# DigitalStethoscope.net
KiCad netlist of a schematic drawn in EAGLE
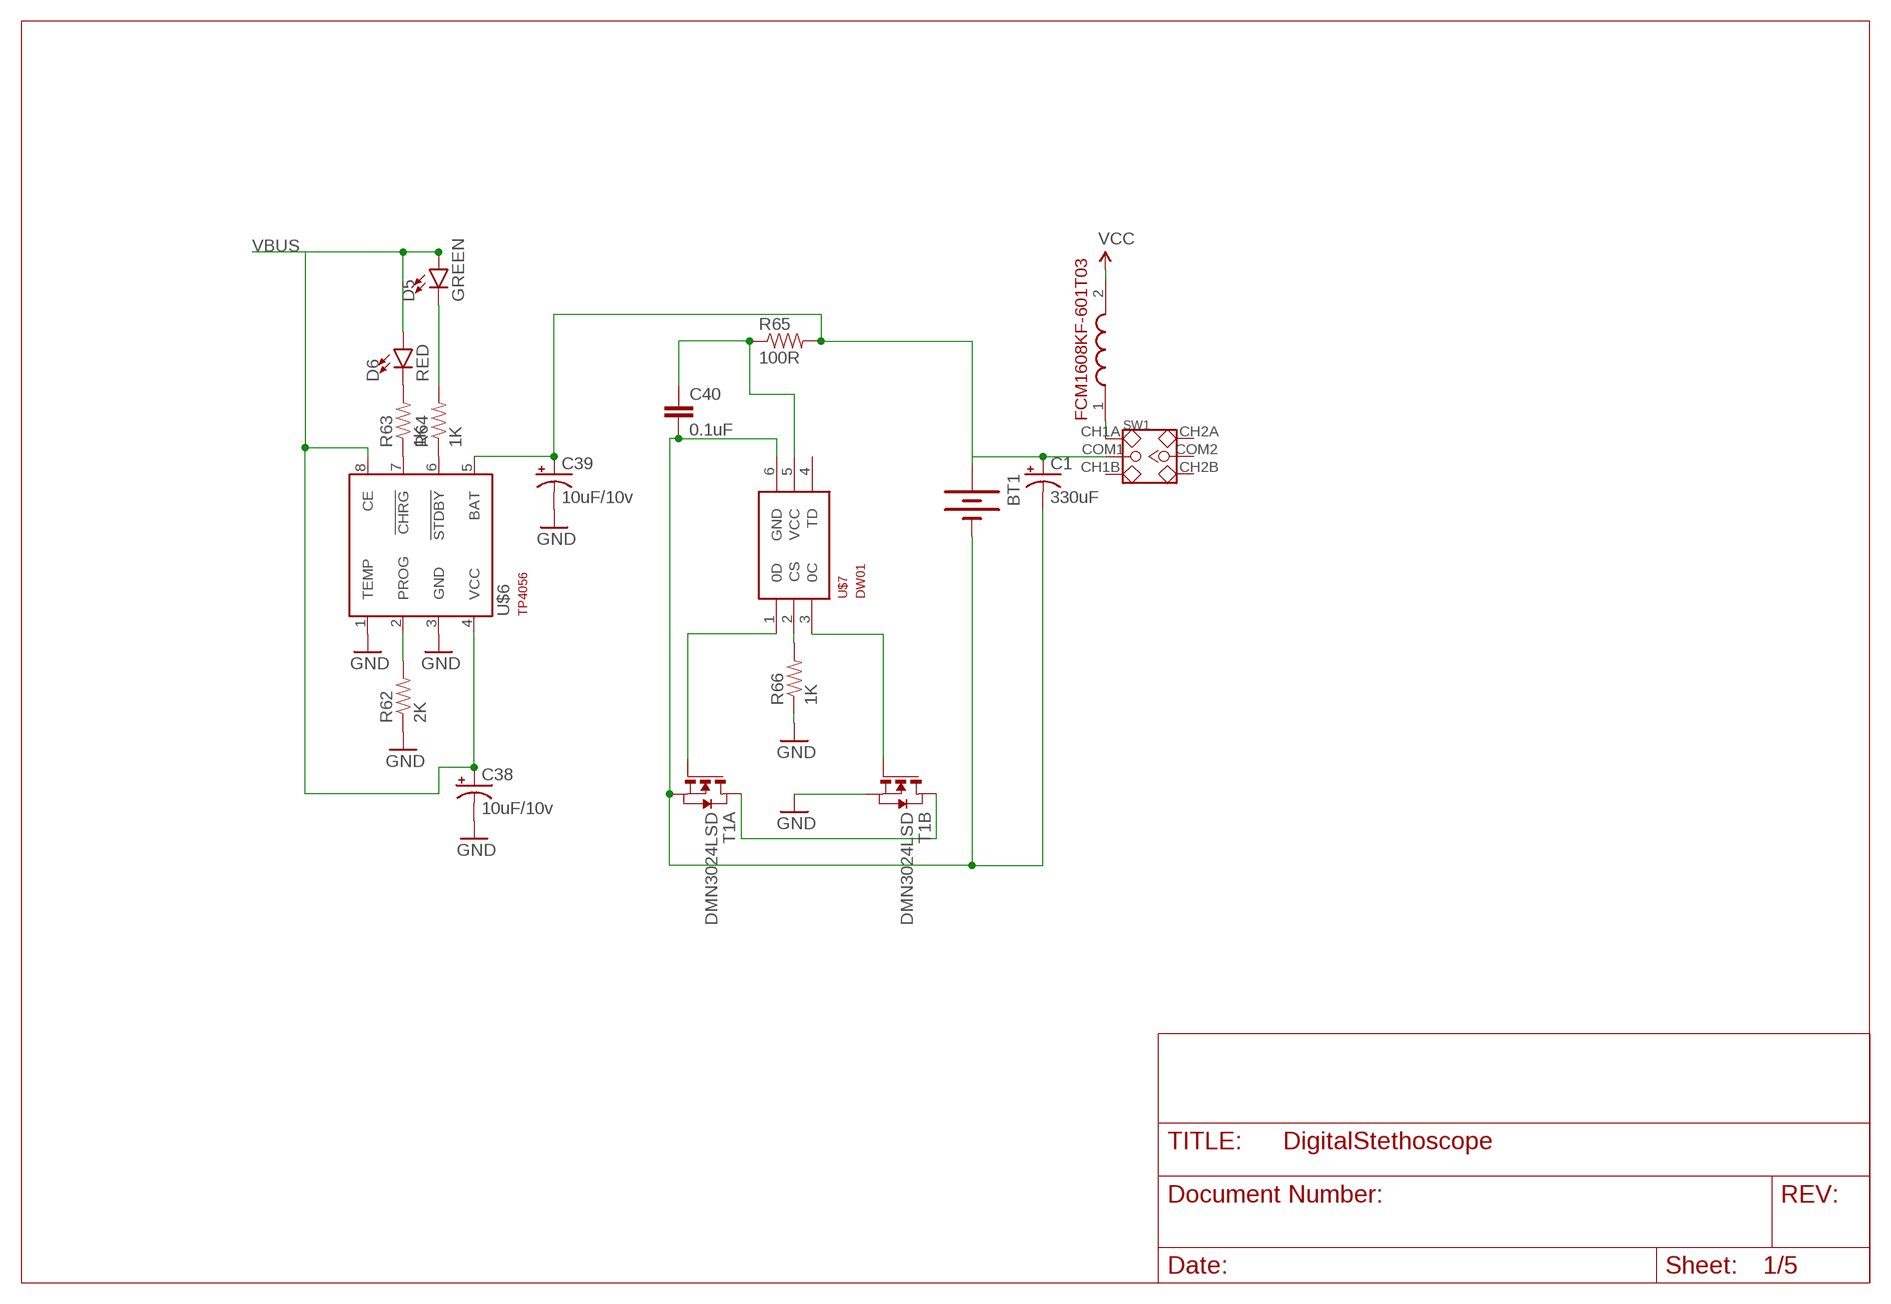
[diagram p0: schematic, sheet 1]
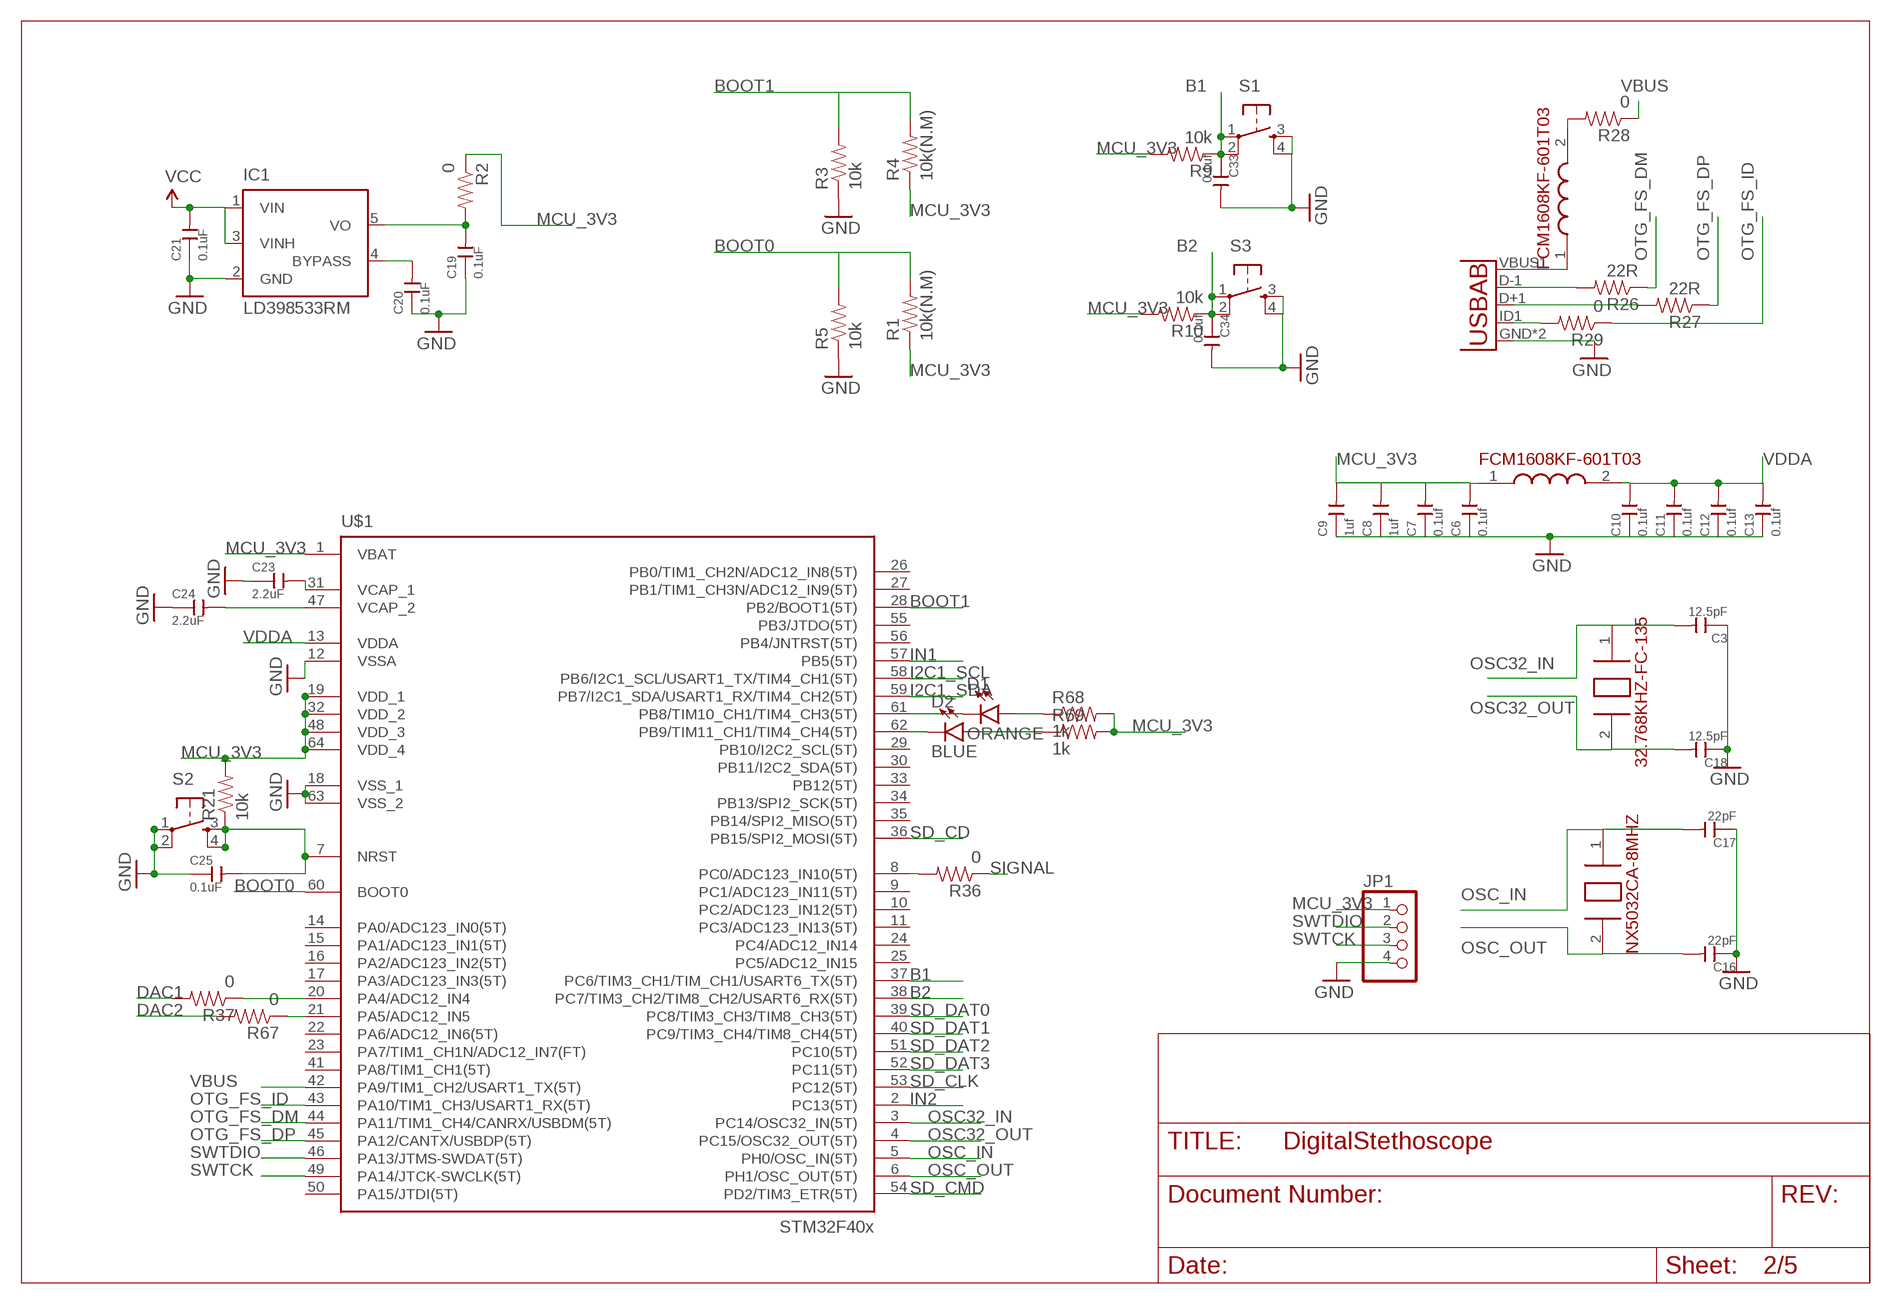
[diagram p1: schematic, sheet 2]
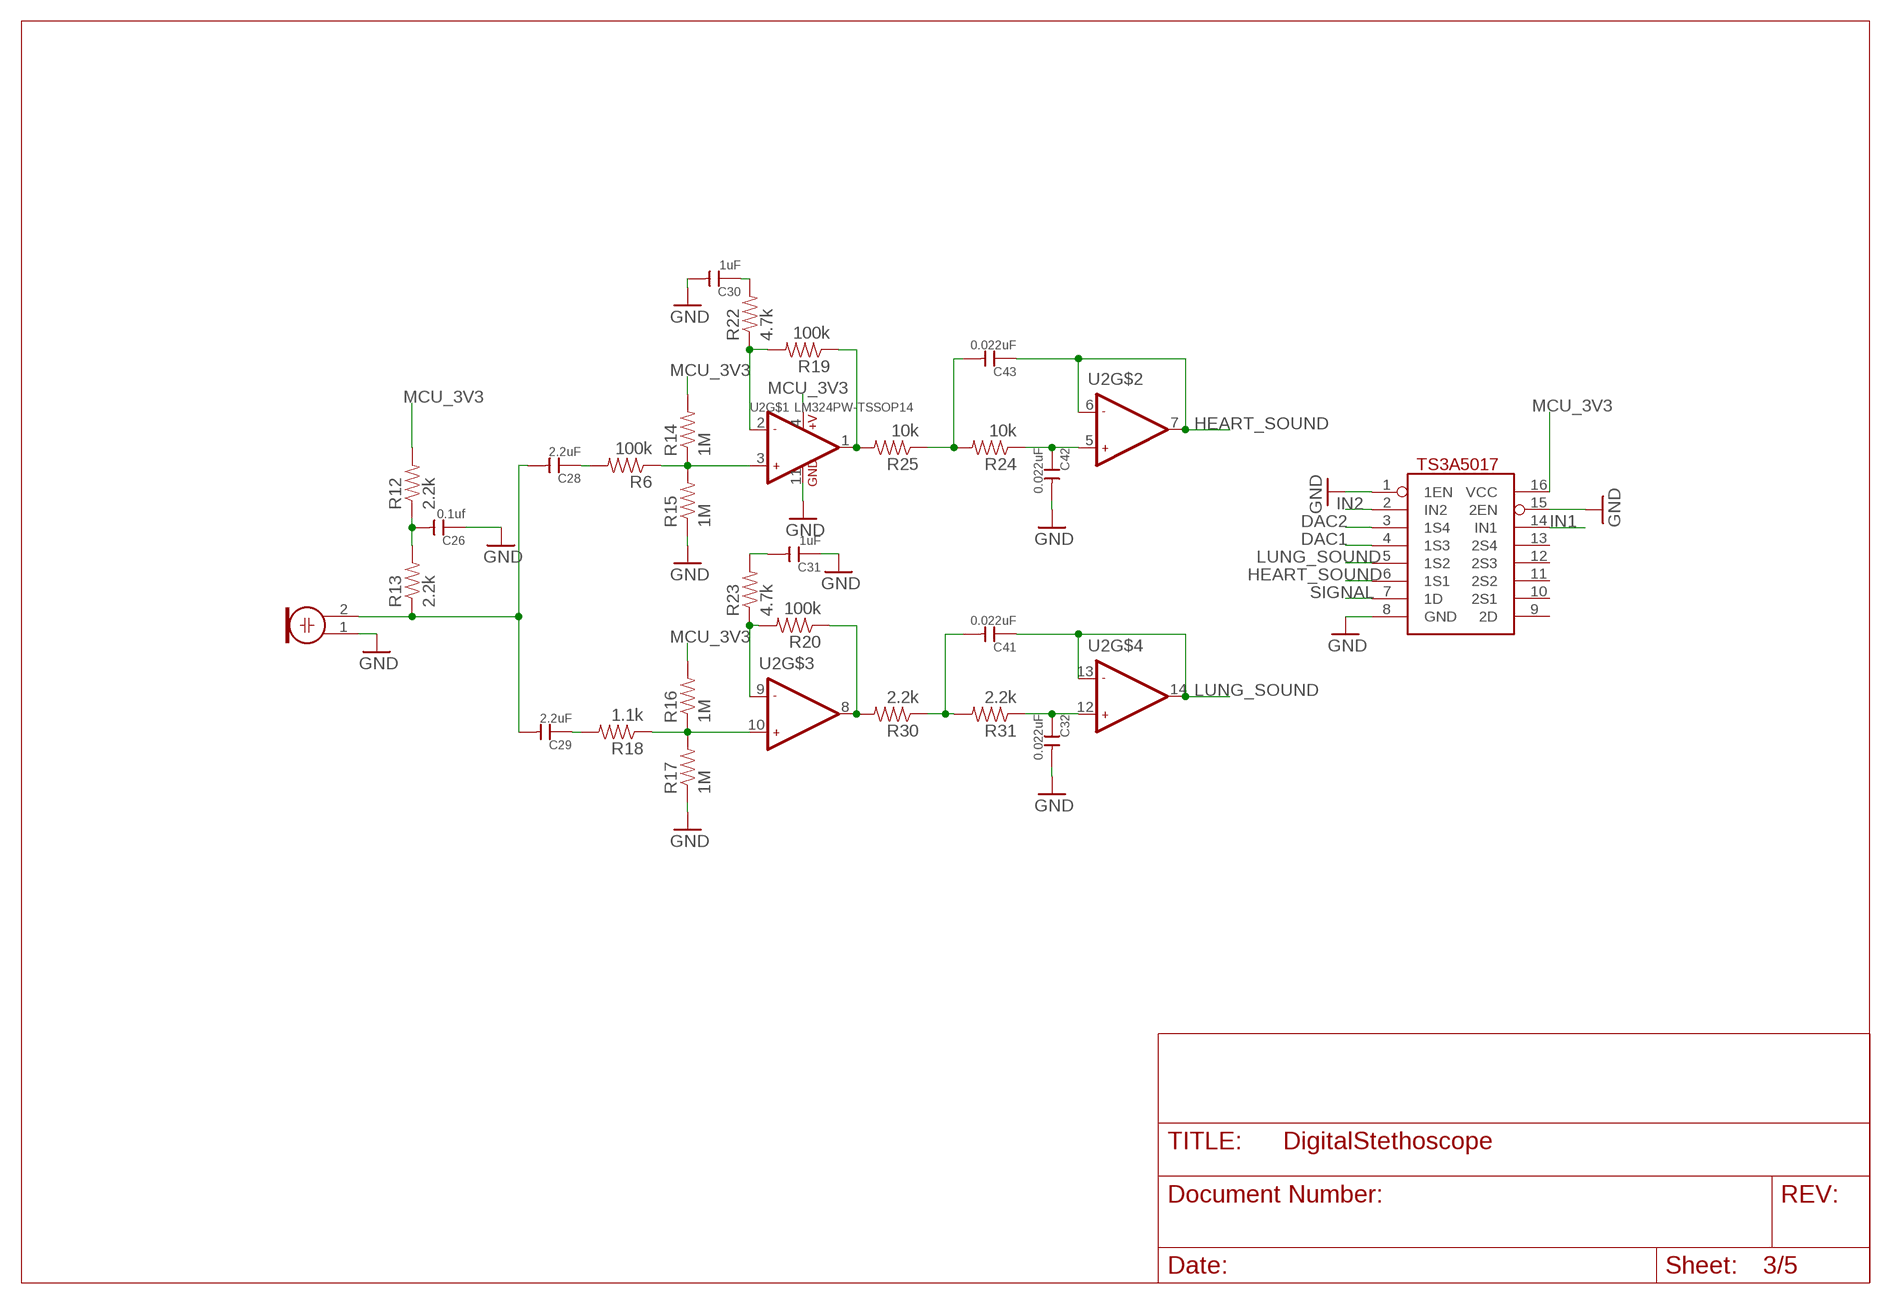
[diagram p2: schematic, sheet 3]
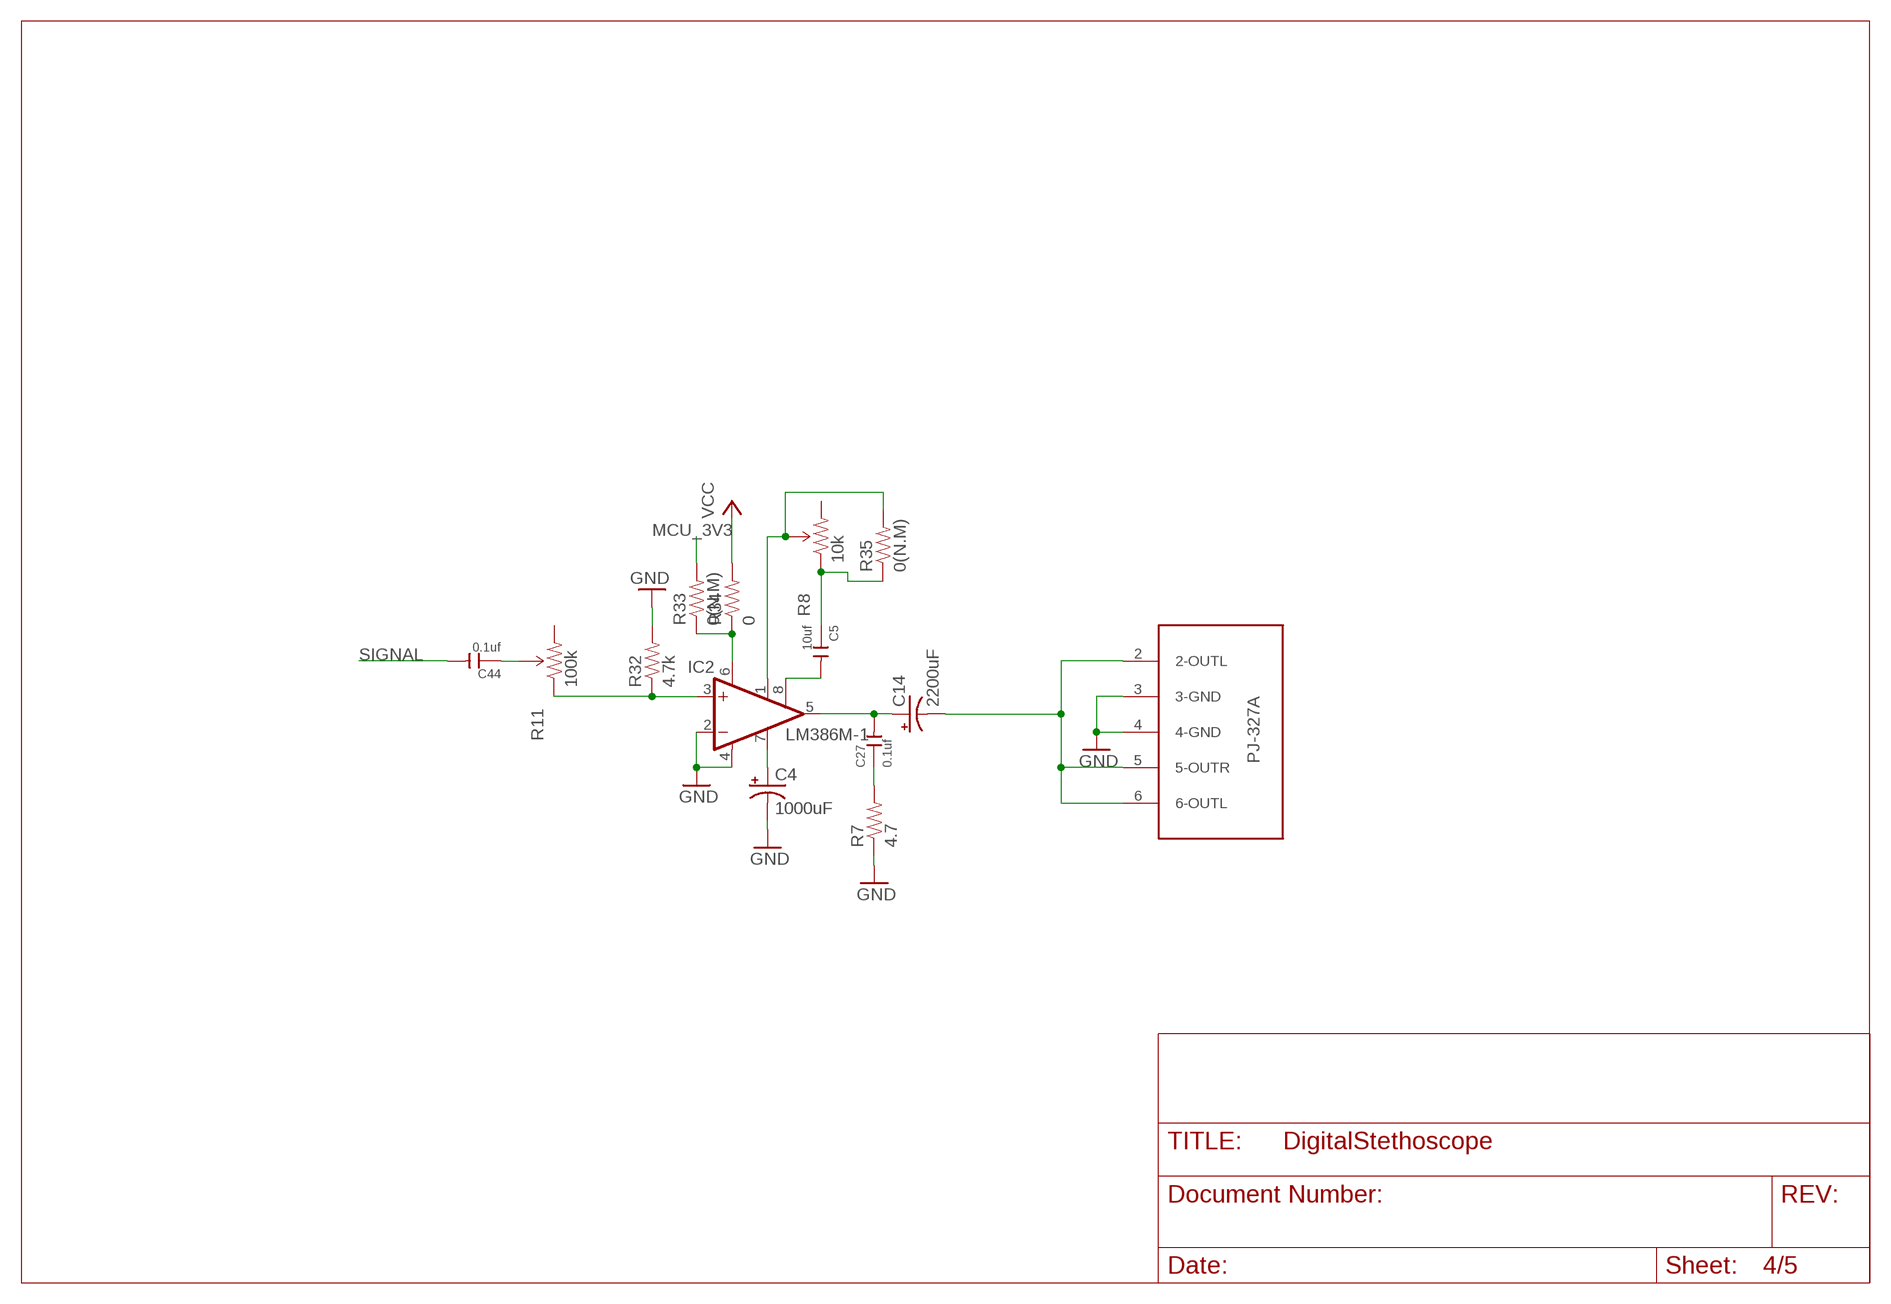
[diagram p3: schematic, sheet 4]
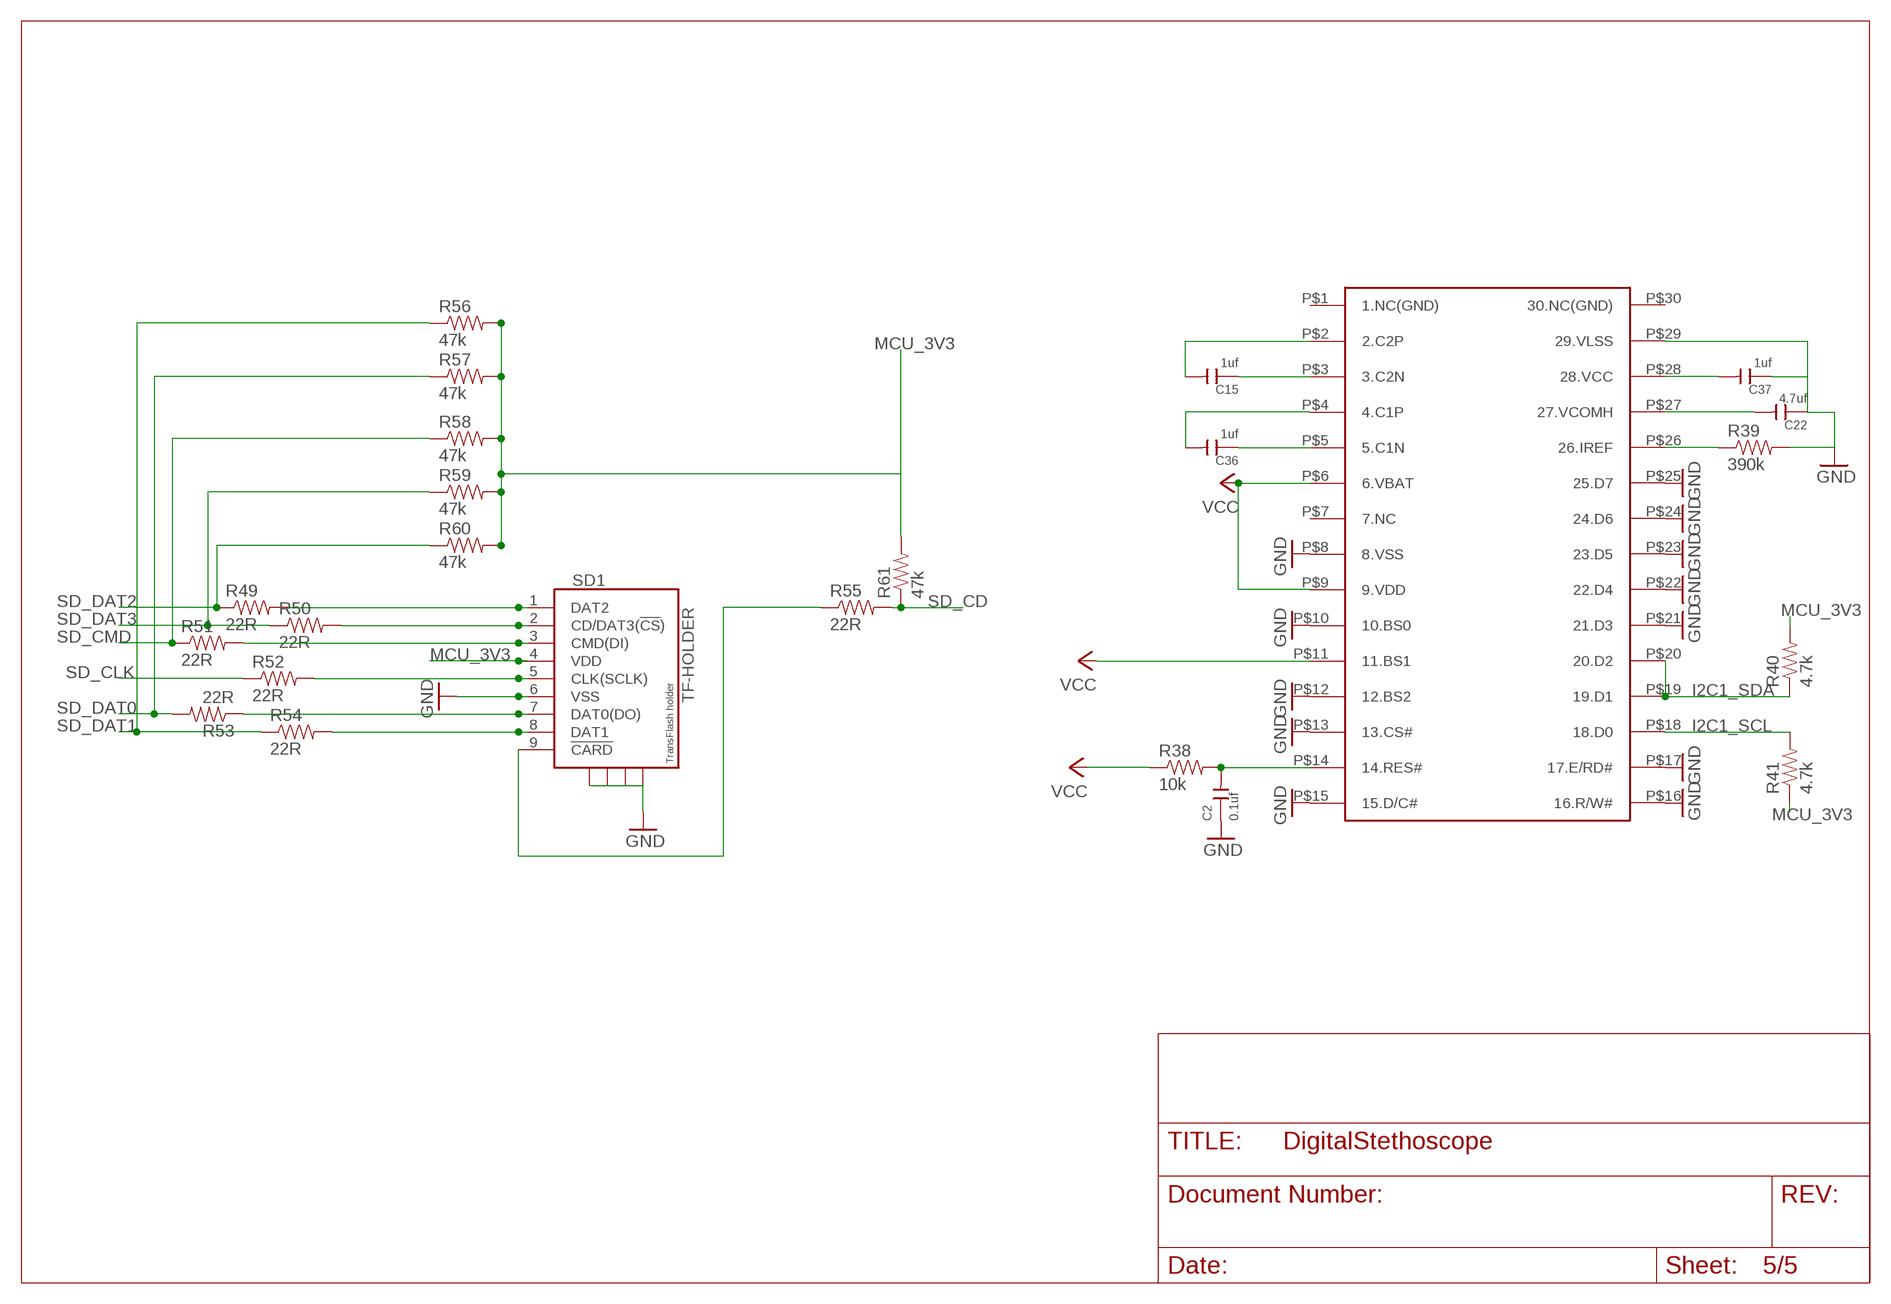
[diagram p4: schematic, sheet 5]

(export (version "E")
  (design (tool "Eeschema 10.0.6"))
  (components
    (comp (ref "C3")
      (value "12.5pF")
      (footprint "eagle-import:C0603")
      (fields (field (name "MPN") "CC0603KRX5R6BB475"))
      (libsource (lib "eagle-import") (part "CERAMIC-4.7UF-10V-10%-X5R(0603)"))
    )
    (comp (ref "C6")
      (value "0.1uf")
      (footprint "eagle-import:C0603")
      (fields (field (name "MPN") "CC0603KRX5R6BB475"))
      (libsource (lib "eagle-import") (part "CERAMIC-4.7UF-10V-10%-X5R(0603)"))
    )
    (comp (ref "C7")
      (value "0.1uf")
      (footprint "eagle-import:C0603")
      (fields (field (name "MPN") "CC0603KRX5R6BB475"))
      (libsource (lib "eagle-import") (part "CERAMIC-4.7UF-10V-10%-X5R(0603)"))
    )
    (comp (ref "C8")
      (value "1uf")
      (footprint "eagle-import:C0603")
      (fields (field (name "MPN") "CC0603KRX5R6BB475"))
      (libsource (lib "eagle-import") (part "CERAMIC-4.7UF-10V-10%-X5R(0603)"))
    )
    (comp (ref "C9")
      (value "1uf")
      (footprint "eagle-import:C0603")
      (fields (field (name "MPN") "CC0603KRX5R6BB475"))
      (libsource (lib "eagle-import") (part "CERAMIC-4.7UF-10V-10%-X5R(0603)"))
    )
    (comp (ref "C10")
      (value "0.1uf")
      (footprint "eagle-import:C0603")
      (fields (field (name "MPN") "CC0603KRX5R6BB475"))
      (libsource (lib "eagle-import") (part "CERAMIC-4.7UF-10V-10%-X5R(0603)"))
    )
    (comp (ref "C11")
      (value "0.1uf")
      (footprint "eagle-import:C0603")
      (fields (field (name "MPN") "CC0603KRX5R6BB475"))
      (libsource (lib "eagle-import") (part "CERAMIC-4.7UF-10V-10%-X5R(0603)"))
    )
    (comp (ref "C12")
      (value "0.1uf")
      (footprint "eagle-import:C0603")
      (fields (field (name "MPN") "CC0603KRX5R6BB475"))
      (libsource (lib "eagle-import") (part "CERAMIC-4.7UF-10V-10%-X5R(0603)"))
    )
    (comp (ref "C13")
      (value "0.1uf")
      (footprint "eagle-import:C0603")
      (fields (field (name "MPN") "CC0603KRX5R6BB475"))
      (libsource (lib "eagle-import") (part "CERAMIC-4.7UF-10V-10%-X5R(0603)"))
    )
    (comp (ref "C16")
      (value "22pF")
      (footprint "eagle-import:C0603")
      (fields (field (name "MPN") "CC0603KRX5R6BB475"))
      (libsource (lib "eagle-import") (part "CERAMIC-4.7UF-10V-10%-X5R(0603)"))
    )
    (comp (ref "C17")
      (value "22pF")
      (footprint "eagle-import:C0603")
      (fields (field (name "MPN") "CC0603KRX5R6BB475"))
      (libsource (lib "eagle-import") (part "CERAMIC-4.7UF-10V-10%-X5R(0603)"))
    )
    (comp (ref "C18")
      (value "12.5pF")
      (footprint "eagle-import:C0603")
      (fields (field (name "MPN") "CC0603KRX5R6BB475"))
      (libsource (lib "eagle-import") (part "CERAMIC-4.7UF-10V-10%-X5R(0603)"))
    )
    (comp (ref "C19")
      (value "0.1uF")
      (footprint "eagle-import:C0603")
      (libsource (lib "eagle-import") (part "CERAMIC-0.5PF-50V-0.1PF-NPO(0603)"))
    )
    (comp (ref "C20")
      (value "0.1uF")
      (footprint "eagle-import:C0603")
      (libsource (lib "eagle-import") (part "CERAMIC-0.5PF-50V-0.1PF-NPO(0603)"))
    )
    (comp (ref "C21")
      (value "0.1uF")
      (footprint "eagle-import:C0603")
      (libsource (lib "eagle-import") (part "CERAMIC-0.5PF-50V-0.1PF-NPO(0603)"))
    )
    (comp (ref "C23")
      (value "2.2uF")
      (footprint "eagle-import:C0603")
      (libsource (lib "eagle-import") (part "CERAMIC-0.5PF-50V-0.1PF-NPO(0603)"))
    )
    (comp (ref "C24")
      (value "2.2uF")
      (footprint "eagle-import:C0603")
      (libsource (lib "eagle-import") (part "CERAMIC-0.5PF-50V-0.1PF-NPO(0603)"))
    )
    (comp (ref "C25")
      (value "0.1uF")
      (footprint "eagle-import:C0603")
      (libsource (lib "eagle-import") (part "CERAMIC-0.5PF-50V-0.1PF-NPO(0603)"))
    )
    (comp (ref "C33")
      (value "0.1uf")
      (footprint "eagle-import:C0603")
      (fields (field (name "MPN") "CC0603KRX5R6BB475"))
      (libsource (lib "eagle-import") (part "CERAMIC-4.7UF-10V-10%-X5R(0603)"))
    )
    (comp (ref "C34")
      (value "0.1uf")
      (footprint "eagle-import:C0603")
      (fields (field (name "MPN") "CC0603KRX5R6BB475"))
      (libsource (lib "eagle-import") (part "CERAMIC-4.7UF-10V-10%-X5R(0603)"))
    )
    (comp (ref "D1")
      (value "ORANGE")
      (footprint "eagle-import:LED-0603")
      (libsource (lib "eagle-import") (part "LED-BLUE0603"))
    )
    (comp (ref "D2")
      (value "BLUE")
      (footprint "eagle-import:LED-0603")
      (libsource (lib "eagle-import") (part "LED-BLUE0603"))
    )
    (comp (ref "IC1")
      (value "LD398533RM")
      (footprint "eagle-import:SOT23-5L")
      (libsource (lib "eagle-import") (part "LD3985M33R"))
    )
    (comp (ref "JP1")
      (value "PINHD-1X4")
      (footprint "eagle-import:1X04")
      (libsource (lib "eagle-import") (part "PINHD-1X4"))
    )
    (comp (ref "R1")
      (value "10k(N.M)")
      (footprint "eagle-import:0603")
      (libsource (lib "eagle-import") (part "0OHM1/10W5%(0603)"))
    )
    (comp (ref "R2")
      (value "0")
      (footprint "eagle-import:0603-RES")
      (libsource (lib "eagle-import") (part "390OHM1/10W1%(0603)"))
    )
    (comp (ref "R3")
      (value "10k")
      (footprint "eagle-import:0603")
      (libsource (lib "eagle-import") (part "0OHM1/10W5%(0603)"))
    )
    (comp (ref "R4")
      (value "10k(N.M)")
      (footprint "eagle-import:0603")
      (libsource (lib "eagle-import") (part "0OHM1/10W5%(0603)"))
    )
    (comp (ref "R5")
      (value "10k")
      (footprint "eagle-import:0603")
      (libsource (lib "eagle-import") (part "0OHM1/10W5%(0603)"))
    )
    (comp (ref "R9")
      (value "10k")
      (footprint "eagle-import:0603")
      (libsource (lib "eagle-import") (part "0OHM1/10W5%(0603)"))
    )
    (comp (ref "R10")
      (value "10k")
      (footprint "eagle-import:0603")
      (libsource (lib "eagle-import") (part "0OHM1/10W5%(0603)"))
    )
    (comp (ref "R21")
      (value "10k")
      (footprint "eagle-import:0603-RES")
      (libsource (lib "eagle-import") (part "390OHM1/10W1%(0603)"))
    )
    (comp (ref "R26")
      (value "22R")
      (footprint "eagle-import:0603-RES")
      (libsource (lib "eagle-import") (part "390OHM1/10W1%(0603)"))
    )
    (comp (ref "R27")
      (value "22R")
      (footprint "eagle-import:0603-RES")
      (libsource (lib "eagle-import") (part "390OHM1/10W1%(0603)"))
    )
    (comp (ref "R28")
      (value "0")
      (footprint "eagle-import:0603-RES")
      (libsource (lib "eagle-import") (part "390OHM1/10W1%(0603)"))
    )
    (comp (ref "R29")
      (value "0")
      (footprint "eagle-import:0603-RES")
      (libsource (lib "eagle-import") (part "390OHM1/10W1%(0603)"))
    )
    (comp (ref "R36")
      (value "0")
      (footprint "eagle-import:0603-RES")
      (libsource (lib "eagle-import") (part "390OHM1/10W1%(0603)"))
    )
    (comp (ref "R37")
      (value "0")
      (footprint "eagle-import:0603-RES")
      (libsource (lib "eagle-import") (part "390OHM1/10W1%(0603)"))
    )
    (comp (ref "R67")
      (value "0")
      (footprint "eagle-import:0603-RES")
      (libsource (lib "eagle-import") (part "390OHM1/10W1%(0603)"))
    )
    (comp (ref "R68")
      (value "1k")
      (footprint "eagle-import:0603-RES")
      (libsource (lib "eagle-import") (part "390OHM1/10W1%(0603)"))
    )
    (comp (ref "R69")
      (value "1k")
      (footprint "eagle-import:0603-RES")
      (libsource (lib "eagle-import") (part "390OHM1/10W1%(0603)"))
    )
    (comp (ref "S1")
      (value "TAC_SWITCHSMD")
      (footprint "eagle-import:TACTILE_SWITCH_SMD")
      (libsource (lib "eagle-import") (part "TAC_SWITCHSMD"))
    )
    (comp (ref "S2")
      (value "TAC_SWITCHSMD")
      (footprint "eagle-import:TACTILE_SWITCH_SMD")
      (libsource (lib "eagle-import") (part "TAC_SWITCHSMD"))
    )
    (comp (ref "S3")
      (value "TAC_SWITCHSMD")
      (footprint "eagle-import:TACTILE_SWITCH_SMD")
      (libsource (lib "eagle-import") (part "TAC_SWITCHSMD"))
    )
    (comp (ref "U$1")
      (value "STM32F405R")
      (footprint "eagle-import:TQFP64")
      (libsource (lib "eagle-import") (part "STM32F405R"))
    )
    (comp (ref "U$2")
      (value "32.768KHZ-FC-135")
      (footprint "eagle-import:32.768KHZ-FC-135")
      (libsource (lib "eagle-import") (part "32.768KHZ-FC-135"))
    )
    (comp (ref "U$3")
      (value "FCM1608KF-601T03")
      (footprint "eagle-import:FCM1608KF-601T03")
      (libsource (lib "eagle-import") (part "FCM1608KF-601T03"))
    )
    (comp (ref "U$5")
      (value "FCM1608KF-601T03")
      (footprint "eagle-import:FCM1608KF-601T03")
      (libsource (lib "eagle-import") (part "FCM1608KF-601T03"))
    )
    (comp (ref "U$8")
      (value "NX5032CA-8MHZ")
      (footprint "eagle-import:NX5032CA-8MHZ")
      (libsource (lib "eagle-import") (part "NX5032CA-8MHZ"))
    )
    (comp (ref "U4")
      (value "USB\"\"")
      (footprint "eagle-import:USB-MICRO-SMD")
      (libsource (lib "eagle-import") (part "USB{dblquote}{dblquote}"))
    )
    (comp (ref "C2")
      (value "0.1uf")
      (footprint "eagle-import:C0603")
      (fields (field (name "MPN") "CC0603KRX5R6BB475"))
      (libsource (lib "eagle-import") (part "CERAMIC-4.7UF-10V-10%-X5R(0603)"))
    )
    (comp (ref "C15")
      (value "1uf")
      (footprint "eagle-import:C0603")
      (fields (field (name "MPN") "CC0603KRX5R6BB475"))
      (libsource (lib "eagle-import") (part "CERAMIC-4.7UF-10V-10%-X5R(0603)"))
    )
    (comp (ref "C22")
      (value "4.7uf")
      (footprint "eagle-import:C0603")
      (fields (field (name "MPN") "CC0603KRX5R6BB475"))
      (libsource (lib "eagle-import") (part "CERAMIC-4.7UF-10V-10%-X5R(0603)"))
    )
    (comp (ref "C36")
      (value "1uf")
      (footprint "eagle-import:C0603")
      (fields (field (name "MPN") "CC0603KRX5R6BB475"))
      (libsource (lib "eagle-import") (part "CERAMIC-4.7UF-10V-10%-X5R(0603)"))
    )
    (comp (ref "C37")
      (value "1uf")
      (footprint "eagle-import:C0603")
      (fields (field (name "MPN") "CC0603KRX5R6BB475"))
      (libsource (lib "eagle-import") (part "CERAMIC-4.7UF-10V-10%-X5R(0603)"))
    )
    (comp (ref "R38")
      (value "10k")
      (footprint "eagle-import:0603")
      (libsource (lib "eagle-import") (part "0OHM1/10W5%(0603)"))
    )
    (comp (ref "R39")
      (value "390k")
      (footprint "eagle-import:0603")
      (libsource (lib "eagle-import") (part "0OHM1/10W5%(0603)"))
    )
    (comp (ref "R40")
      (value "4.7k")
      (footprint "eagle-import:0603")
      (libsource (lib "eagle-import") (part "0OHM1/10W5%(0603)"))
    )
    (comp (ref "R41")
      (value "4.7k")
      (footprint "eagle-import:0603")
      (libsource (lib "eagle-import") (part "0OHM1/10W5%(0603)"))
    )
    (comp (ref "R49")
      (value "22R")
      (footprint "eagle-import:0603-RES")
      (libsource (lib "eagle-import") (part "100OHM1/10W1%(0603)"))
    )
    (comp (ref "R50")
      (value "22R")
      (footprint "eagle-import:0603-RES")
      (libsource (lib "eagle-import") (part "100OHM1/10W1%(0603)"))
    )
    (comp (ref "R51")
      (value "22R")
      (footprint "eagle-import:0603-RES")
      (libsource (lib "eagle-import") (part "100OHM1/10W1%(0603)"))
    )
    (comp (ref "R52")
      (value "22R")
      (footprint "eagle-import:0603-RES")
      (libsource (lib "eagle-import") (part "100OHM1/10W1%(0603)"))
    )
    (comp (ref "R53")
      (value "22R")
      (footprint "eagle-import:0603-RES")
      (libsource (lib "eagle-import") (part "100OHM1/10W1%(0603)"))
    )
    (comp (ref "R54")
      (value "22R")
      (footprint "eagle-import:0603-RES")
      (libsource (lib "eagle-import") (part "100OHM1/10W1%(0603)"))
    )
    (comp (ref "R55")
      (value "22R")
      (footprint "eagle-import:0603-RES")
      (libsource (lib "eagle-import") (part "100OHM1/10W1%(0603)"))
    )
    (comp (ref "R56")
      (value "47k")
      (footprint "eagle-import:0603-RES")
      (libsource (lib "eagle-import") (part "100OHM1/10W1%(0603)"))
    )
    (comp (ref "R57")
      (value "47k")
      (footprint "eagle-import:0603-RES")
      (libsource (lib "eagle-import") (part "100OHM1/10W1%(0603)"))
    )
    (comp (ref "R58")
      (value "47k")
      (footprint "eagle-import:0603-RES")
      (libsource (lib "eagle-import") (part "100OHM1/10W1%(0603)"))
    )
    (comp (ref "R59")
      (value "47k")
      (footprint "eagle-import:0603-RES")
      (libsource (lib "eagle-import") (part "100OHM1/10W1%(0603)"))
    )
    (comp (ref "R60")
      (value "47k")
      (footprint "eagle-import:0603-RES")
      (libsource (lib "eagle-import") (part "100OHM1/10W1%(0603)"))
    )
    (comp (ref "R61")
      (value "47k")
      (footprint "eagle-import:0603-RES")
      (libsource (lib "eagle-import") (part "100OHM1/10W1%(0603)"))
    )
    (comp (ref "SD1")
      (value "TF-HOLDER")
      (footprint "eagle-import:TF-PULL")
      (libsource (lib "eagle-import") (part "TF-HOLDER"))
    )
    (comp (ref "U$18")
      (value "ER-OLED0.96")
      (footprint "eagle-import:ER-OLED0.96")
      (libsource (lib "eagle-import") (part "ER-OLED0.96"))
    )
    (comp (ref "C4")
      (value "1000uF")
      (footprint "eagle-import:E3,5-8")
      (libsource (lib "eagle-import") (part "CPOL-USE3.5-8"))
    )
    (comp (ref "C5")
      (value "10uf")
      (footprint "eagle-import:C0603")
      (fields (field (name "MPN") "CC0603KRX5R6BB475"))
      (libsource (lib "eagle-import") (part "CERAMIC-4.7UF-10V-10%-X5R(0603)"))
    )
    (comp (ref "C14")
      (value "2200uF")
      (footprint "eagle-import:E3,5-8")
      (libsource (lib "eagle-import") (part "CPOL-USE3.5-8"))
    )
    (comp (ref "C27")
      (value "0.1uf")
      (footprint "eagle-import:C0603")
      (fields (field (name "MPN") "CC0603KRX5R6BB475"))
      (libsource (lib "eagle-import") (part "CERAMIC-4.7UF-10V-10%-X5R(0603)"))
    )
    (comp (ref "C44")
      (value "0.1uf")
      (footprint "eagle-import:C0603")
      (fields (field (name "MPN") "CC0603KRX5R6BB475"))
      (libsource (lib "eagle-import") (part "CERAMIC-4.7UF-10V-10%-X5R(0603)"))
    )
    (comp (ref "IC2")
      (value "LM386M-1")
      (footprint "eagle-import:SO08")
      (libsource (lib "eagle-import") (part "LM386?-M1"))
    )
    (comp (ref "R7")
      (value "4.7")
      (footprint "eagle-import:0603-RES")
      (libsource (lib "eagle-import") (part "390OHM1/10W1%(0603)"))
    )
    (comp (ref "R8")
      (value "10k")
      (footprint "eagle-import:TRIMPOT_TC33")
      (libsource (lib "eagle-import") (part "TRIMPOT-2"))
    )
    (comp (ref "R11")
      (value "100k")
      (footprint "eagle-import:TRIMPOT_TC33")
      (libsource (lib "eagle-import") (part "TRIMPOT-2"))
    )
    (comp (ref "R32")
      (value "4.7k")
      (footprint "eagle-import:0603-RES")
      (libsource (lib "eagle-import") (part "390OHM1/10W1%(0603)"))
    )
    (comp (ref "R33")
      (value "0(N.M)")
      (footprint "eagle-import:0603-RES")
      (libsource (lib "eagle-import") (part "390OHM1/10W1%(0603)"))
    )
    (comp (ref "R34")
      (value "0")
      (footprint "eagle-import:0603-RES")
      (libsource (lib "eagle-import") (part "390OHM1/10W1%(0603)"))
    )
    (comp (ref "R35")
      (value "0(N.M)")
      (footprint "eagle-import:0603-RES")
      (libsource (lib "eagle-import") (part "390OHM1/10W1%(0603)"))
    )
    (comp (ref "U$9")
      (value "PJ-327A")
      (footprint "eagle-import:PJ-327A")
      (libsource (lib "eagle-import") (part "PJ-327A"))
    )
    (comp (ref "ASW")
      (value "MUX-TS3A5017")
      (footprint "eagle-import:SO16")
      (libsource (lib "eagle-import") (part "MUX-TS3A5017"))
    )
    (comp (ref "C26")
      (value "0.1uf")
      (footprint "eagle-import:C0603")
      (fields (field (name "MPN") "CC0603KRX5R6BB475"))
      (libsource (lib "eagle-import") (part "CERAMIC-4.7UF-10V-10%-X5R(0603)"))
    )
    (comp (ref "C28")
      (value "2.2uF")
      (footprint "eagle-import:C0603")
      (fields (field (name "MPN") "CC0603KRX5R6BB475"))
      (libsource (lib "eagle-import") (part "CERAMIC-4.7UF-10V-10%-X5R(0603)"))
    )
    (comp (ref "C29")
      (value "2.2uF")
      (footprint "eagle-import:C0603")
      (fields (field (name "MPN") "CC0603KRX5R6BB475"))
      (libsource (lib "eagle-import") (part "CERAMIC-4.7UF-10V-10%-X5R(0603)"))
    )
    (comp (ref "C30")
      (value "1uF")
      (footprint "eagle-import:C0603")
      (fields (field (name "MPN") "CC0603KRX5R6BB475"))
      (libsource (lib "eagle-import") (part "CERAMIC-4.7UF-10V-10%-X5R(0603)"))
    )
    (comp (ref "C31")
      (value "1uF")
      (footprint "eagle-import:C0603")
      (fields (field (name "MPN") "CC0603KRX5R6BB475"))
      (libsource (lib "eagle-import") (part "CERAMIC-4.7UF-10V-10%-X5R(0603)"))
    )
    (comp (ref "C32")
      (value "0.022uF")
      (footprint "eagle-import:C0603")
      (fields (field (name "MPN") "CC0603KRX5R6BB475"))
      (libsource (lib "eagle-import") (part "CERAMIC-4.7UF-10V-10%-X5R(0603)"))
    )
    (comp (ref "C41")
      (value "0.022uF")
      (footprint "eagle-import:C0603")
      (fields (field (name "MPN") "CC0603KRX5R6BB475"))
      (libsource (lib "eagle-import") (part "CERAMIC-4.7UF-10V-10%-X5R(0603)"))
    )
    (comp (ref "C42")
      (value "0.022uF")
      (footprint "eagle-import:C0603")
      (fields (field (name "MPN") "CC0603KRX5R6BB475"))
      (libsource (lib "eagle-import") (part "CERAMIC-4.7UF-10V-10%-X5R(0603)"))
    )
    (comp (ref "C43")
      (value "0.022uF")
      (footprint "eagle-import:C0603")
      (fields (field (name "MPN") "CC0603KRX5R6BB475"))
      (libsource (lib "eagle-import") (part "CERAMIC-4.7UF-10V-10%-X5R(0603)"))
    )
    (comp (ref "M1")
      (value "ELECTRET_MICROPHON-F6035AP")
      (footprint "eagle-import:F6035AP")
      (libsource (lib "eagle-import") (part "ELECTRET_MICROPHON-F6035AP"))
    )
    (comp (ref "R6")
      (value "100k")
      (footprint "eagle-import:0603-RES")
      (libsource (lib "eagle-import") (part "390OHM1/10W1%(0603)"))
    )
    (comp (ref "R12")
      (value "2.2k")
      (footprint "eagle-import:0603-RES")
      (libsource (lib "eagle-import") (part "390OHM1/10W1%(0603)"))
    )
    (comp (ref "R13")
      (value "2.2k")
      (footprint "eagle-import:0603-RES")
      (libsource (lib "eagle-import") (part "390OHM1/10W1%(0603)"))
    )
    (comp (ref "R14")
      (value "1M")
      (footprint "eagle-import:0603-RES")
      (libsource (lib "eagle-import") (part "390OHM1/10W1%(0603)"))
    )
    (comp (ref "R15")
      (value "1M")
      (footprint "eagle-import:0603-RES")
      (libsource (lib "eagle-import") (part "390OHM1/10W1%(0603)"))
    )
    (comp (ref "R16")
      (value "1M")
      (footprint "eagle-import:0603-RES")
      (libsource (lib "eagle-import") (part "390OHM1/10W1%(0603)"))
    )
    (comp (ref "R17")
      (value "1M")
      (footprint "eagle-import:0603-RES")
      (libsource (lib "eagle-import") (part "390OHM1/10W1%(0603)"))
    )
    (comp (ref "R18")
      (value "1.1k")
      (footprint "eagle-import:0603-RES")
      (libsource (lib "eagle-import") (part "390OHM1/10W1%(0603)"))
    )
    (comp (ref "R19")
      (value "100k")
      (footprint "eagle-import:0603-RES")
      (libsource (lib "eagle-import") (part "390OHM1/10W1%(0603)"))
    )
    (comp (ref "R20")
      (value "100k")
      (footprint "eagle-import:0603-RES")
      (libsource (lib "eagle-import") (part "390OHM1/10W1%(0603)"))
    )
    (comp (ref "R22")
      (value "4.7k")
      (footprint "eagle-import:0603-RES")
      (libsource (lib "eagle-import") (part "390OHM1/10W1%(0603)"))
    )
    (comp (ref "R23")
      (value "4.7k")
      (footprint "eagle-import:0603-RES")
      (libsource (lib "eagle-import") (part "390OHM1/10W1%(0603)"))
    )
    (comp (ref "R24")
      (value "10k")
      (footprint "eagle-import:0603-RES")
      (libsource (lib "eagle-import") (part "390OHM1/10W1%(0603)"))
    )
    (comp (ref "R25")
      (value "10k")
      (footprint "eagle-import:0603-RES")
      (libsource (lib "eagle-import") (part "390OHM1/10W1%(0603)"))
    )
    (comp (ref "R30")
      (value "2.2k")
      (footprint "eagle-import:0603-RES")
      (libsource (lib "eagle-import") (part "390OHM1/10W1%(0603)"))
    )
    (comp (ref "R31")
      (value "2.2k")
      (footprint "eagle-import:0603-RES")
      (libsource (lib "eagle-import") (part "390OHM1/10W1%(0603)"))
    )
    (comp (ref "U2")
      (value "LM324PW-TSSOP14")
      (footprint "eagle-import:TSSOP14-0.65-5X4.4MM")
      (fields (field (name "MPN") "LM324PW"))
      (libsource (lib "eagle-import") (part "AMPLIFIER-LM324PW(TSSOP14)"))
    )
    (comp (ref "BT1")
      (value "BATTERYLIPO-TABS")
      (footprint "eagle-import:LIPO-110-TABS")
      (libsource (lib "eagle-import") (part "BATTERYLIPO-TABS"))
    )
    (comp (ref "C1")
      (value "330uF")
      (footprint "eagle-import:E3,5-8")
      (libsource (lib "eagle-import") (part "CPOL-USE3.5-8"))
    )
    (comp (ref "C38")
      (value "10uF/10v")
      (footprint "eagle-import:EIA3216-KIT")
      (libsource (lib "eagle-import") (part "CAP_POL1206-KIT"))
    )
    (comp (ref "C39")
      (value "10uF/10v")
      (footprint "eagle-import:EIA3216-KIT")
      (libsource (lib "eagle-import") (part "CAP_POL1206-KIT"))
    )
    (comp (ref "C40")
      (value "0.1uF")
      (footprint "eagle-import:0603-CAP")
      (libsource (lib "eagle-import") (part "0.1UF-100V-10%(0603)"))
    )
    (comp (ref "D5")
      (value "GREEN")
      (footprint "eagle-import:LED-0603")
      (libsource (lib "eagle-import") (part "LED-BLUE0603"))
    )
    (comp (ref "D6")
      (value "RED")
      (footprint "eagle-import:LED-0603")
      (libsource (lib "eagle-import") (part "LED-BLUE0603"))
    )
    (comp (ref "R62")
      (value "2K")
      (footprint "eagle-import:0603-RES")
      (libsource (lib "eagle-import") (part "1KOHM1/10W1%(0603)"))
    )
    (comp (ref "R63")
      (value "1K")
      (footprint "eagle-import:0603-RES")
      (libsource (lib "eagle-import") (part "1KOHM1/10W1%(0603)"))
    )
    (comp (ref "R64")
      (value "1K")
      (footprint "eagle-import:0603-RES")
      (libsource (lib "eagle-import") (part "1KOHM1/10W1%(0603)"))
    )
    (comp (ref "R65")
      (value "100R")
      (footprint "eagle-import:0603-RES")
      (libsource (lib "eagle-import") (part "1KOHM1/10W1%(0603)"))
    )
    (comp (ref "R66")
      (value "1K")
      (footprint "eagle-import:0603-RES")
      (libsource (lib "eagle-import") (part "1KOHM1/10W1%(0603)"))
    )
    (comp (ref "SW1")
      (value "SMD-TOGGLE-SWITCH-2CH(2X3P-7X3.5MM)")
      (footprint "eagle-import:SW6-2.54-SMD-7.0X3.5X1.5MM")
      (libsource (lib "eagle-import") (part "SMD-TOGGLE-SWITCH-2CH(2X3P-7X3.5MM)"))
    )
    (comp (ref "T1")
      (value "DMN3024LSD")
      (footprint "eagle-import:TSSOP-8")
      (libsource (lib "eagle-import") (part "DMN3024LSD"))
    )
    (comp (ref "U$4")
      (value "FCM1608KF-601T03")
      (footprint "eagle-import:FCM1608KF-601T03")
      (libsource (lib "eagle-import") (part "FCM1608KF-601T03"))
    )
    (comp (ref "U$6")
      (value "TP4056")
      (footprint "eagle-import:SOT23-8")
      (libsource (lib "eagle-import") (part "TP4056"))
    )
    (comp (ref "U$7")
      (value "DW01")
      (footprint "eagle-import:SOT23-6")
      (libsource (lib "eagle-import") (part "DW01"))
    )
  )
  (nets
    (net (code "1") (name "B1") (class "Default")
      (node (ref "C33") (pin "1") (pinfunction "1_1") (pintype "passive"))
      (node (ref "R9") (pin "1") (pinfunction "1_1") (pintype "passive"))
      (node (ref "S1") (pin "1") (pinfunction "1_1") (pintype "passive"))
      (node (ref "S1") (pin "2") (pinfunction "2_2") (pintype "passive"))
      (node (ref "U$1") (pin "37") (pinfunction "PC6/TIM3_CH1/TIM_CH1/USART6_TX(5T)_37") (pintype "bidirectional"))
    )
    (net (code "2") (name "B2") (class "Default")
      (node (ref "C34") (pin "1") (pinfunction "1_1") (pintype "passive"))
      (node (ref "R10") (pin "1") (pinfunction "1_1") (pintype "passive"))
      (node (ref "S3") (pin "1") (pinfunction "1_1") (pintype "passive"))
      (node (ref "S3") (pin "2") (pinfunction "2_2") (pintype "passive"))
      (node (ref "U$1") (pin "38") (pinfunction "PC7/TIM3_CH2/TIM8_CH2/USART6_RX(5T)_38") (pintype "bidirectional"))
    )
    (net (code "3") (name "BOOT0") (class "Default")
      (node (ref "R1") (pin "2") (pinfunction "2_2") (pintype "passive"))
      (node (ref "R5") (pin "2") (pinfunction "2_2") (pintype "passive"))
      (node (ref "U$1") (pin "60") (pinfunction "BOOT0_60") (pintype "bidirectional"))
    )
    (net (code "4") (name "BOOT1") (class "Default")
      (node (ref "R3") (pin "2") (pinfunction "2_2") (pintype "passive"))
      (node (ref "R4") (pin "2") (pinfunction "2_2") (pintype "passive"))
      (node (ref "U$1") (pin "28") (pinfunction "PB2/BOOT1(5T)_28") (pintype "bidirectional"))
    )
    (net (code "5") (name "DAC1") (class "Default")
      (node (ref "ASW") (pin "4") (pinfunction "1S3_4") (pintype "bidirectional"))
      (node (ref "R37") (pin "2") (pinfunction "2_2") (pintype "passive"))
    )
    (net (code "6") (name "DAC2") (class "Default")
      (node (ref "ASW") (pin "3") (pinfunction "1S4_3") (pintype "bidirectional"))
      (node (ref "R67") (pin "2") (pinfunction "2_2") (pintype "passive"))
    )
    (net (code "7") (name "GND") (class "Default")
      (node (ref "ASW") (pin "1") (pinfunction "1EN_1") (pintype "bidirectional"))
      (node (ref "ASW") (pin "15") (pinfunction "2EN_15") (pintype "bidirectional"))
      (node (ref "ASW") (pin "8") (pinfunction "GND_8") (pintype "bidirectional"))
      (node (ref "C10") (pin "1") (pinfunction "1_1") (pintype "passive"))
      (node (ref "C11") (pin "1") (pinfunction "1_1") (pintype "passive"))
      (node (ref "C12") (pin "1") (pinfunction "1_1") (pintype "passive"))
      (node (ref "C13") (pin "1") (pinfunction "1_1") (pintype "passive"))
      (node (ref "C16") (pin "1") (pinfunction "1_1") (pintype "passive"))
      (node (ref "C17") (pin "1") (pinfunction "1_1") (pintype "passive"))
      (node (ref "C18") (pin "1") (pinfunction "1_1") (pintype "passive"))
      (node (ref "C19") (pin "1") (pinfunction "1_1") (pintype "passive"))
      (node (ref "C2") (pin "1") (pinfunction "1_1") (pintype "passive"))
      (node (ref "C20") (pin "1") (pinfunction "1_1") (pintype "passive"))
      (node (ref "C21") (pin "1") (pinfunction "1_1") (pintype "passive"))
      (node (ref "C22") (pin "1") (pinfunction "1_1") (pintype "passive"))
      (node (ref "C23") (pin "1") (pinfunction "1_1") (pintype "passive"))
      (node (ref "C24") (pin "1") (pinfunction "1_1") (pintype "passive"))
      (node (ref "C25") (pin "1") (pinfunction "1_1") (pintype "passive"))
      (node (ref "C26") (pin "1") (pinfunction "1_1") (pintype "passive"))
      (node (ref "C3") (pin "1") (pinfunction "1_1") (pintype "passive"))
      (node (ref "C30") (pin "2") (pinfunction "2_2") (pintype "passive"))
      (node (ref "C31") (pin "1") (pinfunction "1_1") (pintype "passive"))
      (node (ref "C32") (pin "2") (pinfunction "2_2") (pintype "passive"))
      (node (ref "C33") (pin "2") (pinfunction "2_2") (pintype "passive"))
      (node (ref "C34") (pin "2") (pinfunction "2_2") (pintype "passive"))
      (node (ref "C37") (pin "1") (pinfunction "1_1") (pintype "passive"))
      (node (ref "C38") (pin "C") (pinfunction "-_C") (pintype "passive"))
      (node (ref "C39") (pin "C") (pinfunction "-_C") (pintype "passive"))
      (node (ref "C4") (pin "-") (pinfunction "-_-") (pintype "passive"))
      (node (ref "C42") (pin "2") (pinfunction "2_2") (pintype "passive"))
      (node (ref "C6") (pin "1") (pinfunction "1_1") (pintype "passive"))
      (node (ref "C7") (pin "1") (pinfunction "1_1") (pintype "passive"))
      (node (ref "C8") (pin "1") (pinfunction "1_1") (pintype "passive"))
      (node (ref "C9") (pin "1") (pinfunction "1_1") (pintype "passive"))
      (node (ref "IC1") (pin "2") (pinfunction "GND_2") (pintype "power_in"))
      (node (ref "IC2") (pin "2") (pinfunction "-IN_2") (pintype "input"))
      (node (ref "IC2") (pin "4") (pinfunction "GND_4") (pintype "power_in"))
      (node (ref "JP1") (pin "4") (pinfunction "4_4") (pintype "passive"))
      (node (ref "M1") (pin "1") (pinfunction "1_1") (pintype "passive"))
      (node (ref "R15") (pin "1") (pinfunction "1_1") (pintype "passive"))
      (node (ref "R17") (pin "1") (pinfunction "1_1") (pintype "passive"))
      (node (ref "R3") (pin "1") (pinfunction "1_1") (pintype "passive"))
      (node (ref "R32") (pin "2") (pinfunction "2_2") (pintype "passive"))
      (node (ref "R39") (pin "2") (pinfunction "2_2") (pintype "passive"))
      (node (ref "R5") (pin "1") (pinfunction "1_1") (pintype "passive"))
      (node (ref "R62") (pin "1") (pinfunction "1_1") (pintype "passive"))
      (node (ref "R66") (pin "1") (pinfunction "1_1") (pintype "passive"))
      (node (ref "R7") (pin "1") (pinfunction "1_1") (pintype "passive"))
      (node (ref "S1") (pin "3") (pinfunction "3_3") (pintype "passive"))
      (node (ref "S1") (pin "4") (pinfunction "4_4") (pintype "passive"))
      (node (ref "S2") (pin "1") (pinfunction "1_1") (pintype "passive"))
      (node (ref "S2") (pin "2") (pinfunction "2_2") (pintype "passive"))
      (node (ref "S3") (pin "3") (pinfunction "3_3") (pintype "passive"))
      (node (ref "S3") (pin "4") (pinfunction "4_4") (pintype "passive"))
      (node (ref "SD1") (pin "6") (pinfunction "VSS_6") (pintype "power_in"))
      (node (ref "SD1") (pin "S1") (pinfunction "S1_S1") (pintype "passive"))
      (node (ref "SD1") (pin "S2") (pinfunction "S2_S2") (pintype "passive"))
      (node (ref "SD1") (pin "S3") (pinfunction "S3_S3") (pintype "passive"))
      (node (ref "SD1") (pin "S4") (pinfunction "S4_S4") (pintype "passive"))
      (node (ref "T1") (pin "6") (pinfunction "S_6") (pintype "passive"))
      (node (ref "T1") (pin "7") (pinfunction "S_7") (pintype "passive"))
      (node (ref "U$1") (pin "12") (pinfunction "VSSA_12") (pintype "bidirectional"))
      (node (ref "U$1") (pin "18") (pinfunction "VSS_1_18") (pintype "bidirectional"))
      (node (ref "U$1") (pin "63") (pinfunction "VSS_2_63") (pintype "bidirectional"))
      (node (ref "U$18") (pin "P$10") (pinfunction "10.BS0_P$10") (pintype "bidirectional"))
      (node (ref "U$18") (pin "P$12") (pinfunction "12.BS2_P$12") (pintype "bidirectional"))
      (node (ref "U$18") (pin "P$13") (pinfunction "13.CS#_P$13") (pintype "bidirectional"))
      (node (ref "U$18") (pin "P$15") (pinfunction "15.D/C#_P$15") (pintype "bidirectional"))
      (node (ref "U$18") (pin "P$16") (pinfunction "16.R/W#_P$16") (pintype "bidirectional"))
      (node (ref "U$18") (pin "P$17") (pinfunction "17.E/RD#_P$17") (pintype "bidirectional"))
      (node (ref "U$18") (pin "P$21") (pinfunction "21.D3_P$21") (pintype "bidirectional"))
      (node (ref "U$18") (pin "P$22") (pinfunction "22.D4_P$22") (pintype "bidirectional"))
      (node (ref "U$18") (pin "P$23") (pinfunction "23.D5_P$23") (pintype "bidirectional"))
      (node (ref "U$18") (pin "P$24") (pinfunction "24.D6_P$24") (pintype "bidirectional"))
      (node (ref "U$18") (pin "P$25") (pinfunction "25.D7_P$25") (pintype "bidirectional"))
      (node (ref "U$18") (pin "P$29") (pinfunction "29.VLSS_P$29") (pintype "bidirectional"))
      (node (ref "U$18") (pin "P$8") (pinfunction "8.VSS_P$8") (pintype "bidirectional"))
      (node (ref "U$6") (pin "1") (pinfunction "TEMP_1") (pintype "bidirectional"))
      (node (ref "U$6") (pin "3") (pinfunction "GND_3") (pintype "bidirectional"))
      (node (ref "U$9") (pin "3") (pinfunction "3-GND_3") (pintype "bidirectional"))
      (node (ref "U$9") (pin "4") (pinfunction "4-GND_4") (pintype "bidirectional"))
      (node (ref "U2") (pin "11") (pinfunction "GND_11") (pintype "power_in"))
      (node (ref "U4") (pin "GND") (pinfunction "GND_GND") (pintype "bidirectional"))
      (node (ref "U4") (pin "GND1") (pinfunction "GND_GND1") (pintype "bidirectional"))
    )
    (net (code "8") (name "HEART_SOUND") (class "Default")
      (node (ref "ASW") (pin "6") (pinfunction "1S1_6") (pintype "bidirectional"))
      (node (ref "C43") (pin "1") (pinfunction "1_1") (pintype "passive"))
      (node (ref "U2") (pin "6") (pinfunction "-IN2_6") (pintype "input"))
      (node (ref "U2") (pin "7") (pinfunction "OUT2_7") (pintype "output"))
    )
    (net (code "9") (name "I2C1_SCL") (class "Default")
      (node (ref "R41") (pin "2") (pinfunction "2_2") (pintype "passive"))
      (node (ref "U$1") (pin "58") (pinfunction "PB6/I2C1_SCL/USART1_TX/TIM4_CH1(5T)_58") (pintype "bidirectional"))
      (node (ref "U$18") (pin "P$18") (pinfunction "18.D0_P$18") (pintype "bidirectional"))
    )
    (net (code "10") (name "I2C1_SDA") (class "Default")
      (node (ref "R40") (pin "1") (pinfunction "1_1") (pintype "passive"))
      (node (ref "U$1") (pin "59") (pinfunction "PB7/I2C1_SDA/USART1_RX/TIM4_CH2(5T)_59") (pintype "bidirectional"))
      (node (ref "U$18") (pin "P$19") (pinfunction "19.D1_P$19") (pintype "bidirectional"))
      (node (ref "U$18") (pin "P$20") (pinfunction "20.D2_P$20") (pintype "bidirectional"))
    )
    (net (code "11") (name "IN1") (class "Default")
      (node (ref "ASW") (pin "14") (pinfunction "IN1_14") (pintype "bidirectional"))
      (node (ref "U$1") (pin "57") (pinfunction "PB5(5T)_57") (pintype "bidirectional"))
    )
    (net (code "12") (name "IN2") (class "Default")
      (node (ref "ASW") (pin "2") (pinfunction "IN2_2") (pintype "bidirectional"))
      (node (ref "U$1") (pin "2") (pinfunction "PC13(5T)_2") (pintype "bidirectional"))
    )
    (net (code "13") (name "LUNG_SOUND") (class "Default")
      (node (ref "ASW") (pin "5") (pinfunction "1S2_5") (pintype "bidirectional"))
      (node (ref "C41") (pin "1") (pinfunction "1_1") (pintype "passive"))
      (node (ref "U2") (pin "13") (pinfunction "-IN2_13") (pintype "input"))
      (node (ref "U2") (pin "14") (pinfunction "OUT2_14") (pintype "output"))
    )
    (net (code "14") (name "MCU_3V3") (class "Default")
      (node (ref "ASW") (pin "16") (pinfunction "VCC_16") (pintype "bidirectional"))
      (node (ref "C6") (pin "2") (pinfunction "2_2") (pintype "passive"))
      (node (ref "C7") (pin "2") (pinfunction "2_2") (pintype "passive"))
      (node (ref "C8") (pin "2") (pinfunction "2_2") (pintype "passive"))
      (node (ref "C9") (pin "2") (pinfunction "2_2") (pintype "passive"))
      (node (ref "JP1") (pin "1") (pinfunction "1_1") (pintype "passive"))
      (node (ref "R1") (pin "1") (pinfunction "1_1") (pintype "passive"))
      (node (ref "R10") (pin "2") (pinfunction "2_2") (pintype "passive"))
      (node (ref "R12") (pin "2") (pinfunction "2_2") (pintype "passive"))
      (node (ref "R14") (pin "2") (pinfunction "2_2") (pintype "passive"))
      (node (ref "R16") (pin "2") (pinfunction "2_2") (pintype "passive"))
      (node (ref "R2") (pin "1") (pinfunction "1_1") (pintype "passive"))
      (node (ref "R21") (pin "2") (pinfunction "2_2") (pintype "passive"))
      (node (ref "R33") (pin "2") (pinfunction "2_2") (pintype "passive"))
      (node (ref "R4") (pin "1") (pinfunction "1_1") (pintype "passive"))
      (node (ref "R40") (pin "2") (pinfunction "2_2") (pintype "passive"))
      (node (ref "R41") (pin "1") (pinfunction "1_1") (pintype "passive"))
      (node (ref "R56") (pin "2") (pinfunction "2_2") (pintype "passive"))
      (node (ref "R57") (pin "2") (pinfunction "2_2") (pintype "passive"))
      (node (ref "R58") (pin "2") (pinfunction "2_2") (pintype "passive"))
      (node (ref "R59") (pin "2") (pinfunction "2_2") (pintype "passive"))
      (node (ref "R60") (pin "2") (pinfunction "2_2") (pintype "passive"))
      (node (ref "R61") (pin "2") (pinfunction "2_2") (pintype "passive"))
      (node (ref "R68") (pin "2") (pinfunction "2_2") (pintype "passive"))
      (node (ref "R69") (pin "2") (pinfunction "2_2") (pintype "passive"))
      (node (ref "R9") (pin "2") (pinfunction "2_2") (pintype "passive"))
      (node (ref "SD1") (pin "4") (pinfunction "VDD_4") (pintype "power_in"))
      (node (ref "U$1") (pin "1") (pinfunction "VBAT_1") (pintype "bidirectional"))
      (node (ref "U$1") (pin "19") (pinfunction "VDD_1_19") (pintype "bidirectional"))
      (node (ref "U$1") (pin "32") (pinfunction "VDD_2_32") (pintype "bidirectional"))
      (node (ref "U$1") (pin "48") (pinfunction "VDD_3_48") (pintype "bidirectional"))
      (node (ref "U$1") (pin "64") (pinfunction "VDD_4_64") (pintype "bidirectional"))
      (node (ref "U$3") (pin "1") (pinfunction "1.IN_1") (pintype "bidirectional"))
      (node (ref "U2") (pin "4") (pinfunction "+V_4") (pintype "power_in"))
    )
    (net (code "15") (name "Net-(C5-Pad2)") (class "Default")
      (node (ref "C5") (pin "2") (pinfunction "2_2") (pintype "passive"))
      (node (ref "IC2") (pin "8") (pinfunction "GAIN_8") (pintype "passive"))
    )
    (net (code "16") (name "Net-(C26-Pad2)") (class "Default")
      (node (ref "C26") (pin "2") (pinfunction "2_2") (pintype "passive"))
      (node (ref "R12") (pin "1") (pinfunction "1_1") (pintype "passive"))
      (node (ref "R13") (pin "2") (pinfunction "2_2") (pintype "passive"))
    )
    (net (code "17") (name "Net-(C27-Pad1)") (class "Default")
      (node (ref "C27") (pin "1") (pinfunction "1_1") (pintype "passive"))
      (node (ref "R7") (pin "2") (pinfunction "2_2") (pintype "passive"))
    )
    (net (code "18") (name "Net-(C28-Pad1)") (class "Default")
      (node (ref "C28") (pin "1") (pinfunction "1_1") (pintype "passive"))
      (node (ref "R6") (pin "2") (pinfunction "2_2") (pintype "passive"))
    )
    (net (code "19") (name "Net-(C28-Pad2)") (class "Default")
      (node (ref "C28") (pin "2") (pinfunction "2_2") (pintype "passive"))
      (node (ref "C29") (pin "2") (pinfunction "2_2") (pintype "passive"))
      (node (ref "M1") (pin "2") (pinfunction "2_2") (pintype "passive"))
      (node (ref "R13") (pin "1") (pinfunction "1_1") (pintype "passive"))
    )
    (net (code "20") (name "Net-(C29-Pad1)") (class "Default")
      (node (ref "C29") (pin "1") (pinfunction "1_1") (pintype "passive"))
      (node (ref "R18") (pin "2") (pinfunction "2_2") (pintype "passive"))
    )
    (net (code "21") (name "Net-(C30-Pad1)") (class "Default")
      (node (ref "C30") (pin "1") (pinfunction "1_1") (pintype "passive"))
      (node (ref "R22") (pin "2") (pinfunction "2_2") (pintype "passive"))
    )
    (net (code "22") (name "Net-(C31-Pad2)") (class "Default")
      (node (ref "C31") (pin "2") (pinfunction "2_2") (pintype "passive"))
      (node (ref "R23") (pin "2") (pinfunction "2_2") (pintype "passive"))
    )
    (net (code "23") (name "Net-(C39-+)") (class "Default")
      (node (ref "BT1") (pin "+") (pinfunction "+_+") (pintype "power_in"))
      (node (ref "C1") (pin "+") (pinfunction "+_+") (pintype "passive"))
      (node (ref "C39") (pin "A") (pinfunction "+_A") (pintype "passive"))
      (node (ref "R65") (pin "2") (pinfunction "2_2") (pintype "passive"))
      (node (ref "SW1") (pin "COM1") (pinfunction "COM1_COM1") (pintype "bidirectional"))
      (node (ref "U$6") (pin "5") (pinfunction "BAT_5") (pintype "bidirectional"))
    )
    (net (code "24") (name "Net-(C41-Pad2)") (class "Default")
      (node (ref "C41") (pin "2") (pinfunction "2_2") (pintype "passive"))
      (node (ref "R30") (pin "1") (pinfunction "1_1") (pintype "passive"))
      (node (ref "R31") (pin "2") (pinfunction "2_2") (pintype "passive"))
    )
    (net (code "25") (name "Net-(C43-Pad2)") (class "Default")
      (node (ref "C43") (pin "2") (pinfunction "2_2") (pintype "passive"))
      (node (ref "R24") (pin "2") (pinfunction "2_2") (pintype "passive"))
      (node (ref "R25") (pin "1") (pinfunction "1_1") (pintype "passive"))
    )
    (net (code "26") (name "Net-(D1-PadA)") (class "Default")
      (node (ref "D1") (pin "A") (pinfunction "A_A") (pintype "passive"))
      (node (ref "R68") (pin "1") (pinfunction "1_1") (pintype "passive"))
    )
    (net (code "27") (name "Net-(D2-PadA)") (class "Default")
      (node (ref "D2") (pin "A") (pinfunction "A_A") (pintype "passive"))
      (node (ref "R69") (pin "1") (pinfunction "1_1") (pintype "passive"))
    )
    (net (code "28") (name "Net-(D5-PadC)") (class "Default")
      (node (ref "D5") (pin "C") (pinfunction "C_C") (pintype "passive"))
      (node (ref "R64") (pin "2") (pinfunction "2_2") (pintype "passive"))
    )
    (net (code "29") (name "Net-(D6-PadC)") (class "Default")
      (node (ref "D6") (pin "C") (pinfunction "C_C") (pintype "passive"))
      (node (ref "R63") (pin "2") (pinfunction "2_2") (pintype "passive"))
    )
    (net (code "30") (name "Net-(IC1-BYPASS)") (class "Default")
      (node (ref "C20") (pin "2") (pinfunction "2_2") (pintype "passive"))
      (node (ref "IC1") (pin "4") (pinfunction "BYPASS_4") (pintype "passive"))
    )
    (net (code "31") (name "Net-(IC1-VO)") (class "Default")
      (node (ref "C19") (pin "2") (pinfunction "2_2") (pintype "passive"))
      (node (ref "IC1") (pin "5") (pinfunction "VO_5") (pintype "output"))
      (node (ref "R2") (pin "2") (pinfunction "2_2") (pintype "passive"))
    )
    (net (code "32") (name "Net-(IC2-+IN)") (class "Default")
      (node (ref "IC2") (pin "3") (pinfunction "+IN_3") (pintype "input"))
      (node (ref "R11") (pin "1") (pinfunction "CCW_1") (pintype "passive"))
      (node (ref "R32") (pin "1") (pinfunction "1_1") (pintype "passive"))
    )
    (net (code "33") (name "Net-(IC2-BYPASS)") (class "Default")
      (node (ref "C4") (pin "+") (pinfunction "+_+") (pintype "passive"))
      (node (ref "IC2") (pin "7") (pinfunction "BYPASS_7") (pintype "passive"))
    )
    (net (code "34") (name "Net-(IC2-OUT)") (class "Default")
      (node (ref "C14") (pin "+") (pinfunction "+_+") (pintype "passive"))
      (node (ref "C27") (pin "2") (pinfunction "2_2") (pintype "passive"))
      (node (ref "IC2") (pin "5") (pinfunction "OUT_5") (pintype "output"))
    )
    (net (code "35") (name "Net-(IC2-VS)") (class "Default")
      (node (ref "IC2") (pin "6") (pinfunction "VS_6") (pintype "power_in"))
      (node (ref "R33") (pin "1") (pinfunction "1_1") (pintype "passive"))
      (node (ref "R34") (pin "1") (pinfunction "1_1") (pintype "passive"))
    )
    (net (code "36") (name "Net-(R8-CCW)") (class "Default")
      (node (ref "C5") (pin "1") (pinfunction "1_1") (pintype "passive"))
      (node (ref "R35") (pin "1") (pinfunction "1_1") (pintype "passive"))
      (node (ref "R8") (pin "1") (pinfunction "CCW_1") (pintype "passive"))
    )
    (net (code "37") (name "Net-(R8-WIPER)") (class "Default")
      (node (ref "IC2") (pin "1") (pinfunction "GAIN_1") (pintype "passive"))
      (node (ref "R35") (pin "2") (pinfunction "2_2") (pintype "passive"))
      (node (ref "R8") (pin "2") (pinfunction "WIPER_2") (pintype "passive"))
    )
    (net (code "38") (name "Net-(R11-WIPER)") (class "Default")
      (node (ref "C44") (pin "1") (pinfunction "1_1") (pintype "passive"))
      (node (ref "R11") (pin "2") (pinfunction "WIPER_2") (pintype "passive"))
    )
    (net (code "39") (name "Net-(SD1-CD{slash}DAT3(~{CS}))") (class "Default")
      (node (ref "R50") (pin "2") (pinfunction "2_2") (pintype "passive"))
      (node (ref "SD1") (pin "2") (pinfunction "CD/DAT3(~{CS})_2") (pintype "bidirectional"))
    )
    (net (code "40") (name "Net-(SD1-CLK(SCLK))") (class "Default")
      (node (ref "R52") (pin "2") (pinfunction "2_2") (pintype "passive"))
      (node (ref "SD1") (pin "5") (pinfunction "CLK(SCLK)_5") (pintype "input"))
    )
    (net (code "41") (name "Net-(SD1-CMD(DI))") (class "Default")
      (node (ref "R51") (pin "2") (pinfunction "2_2") (pintype "passive"))
      (node (ref "SD1") (pin "3") (pinfunction "CMD(DI)_3") (pintype "bidirectional"))
    )
    (net (code "42") (name "Net-(SD1-DAT0(DO))") (class "Default")
      (node (ref "R53") (pin "1") (pinfunction "1_1") (pintype "passive"))
      (node (ref "SD1") (pin "7") (pinfunction "DAT0(DO)_7") (pintype "bidirectional"))
    )
    (net (code "43") (name "Net-(SD1-DAT1)") (class "Default")
      (node (ref "R54") (pin "2") (pinfunction "2_2") (pintype "passive"))
      (node (ref "SD1") (pin "8") (pinfunction "DAT1_8") (pintype "bidirectional"))
    )
    (net (code "44") (name "Net-(SD1-DAT2)") (class "Default")
      (node (ref "R49") (pin "2") (pinfunction "2_2") (pintype "passive"))
      (node (ref "SD1") (pin "1") (pinfunction "DAT2_1") (pintype "bidirectional"))
    )
    (net (code "45") (name "Net-(SD1-~{CARD})") (class "Default")
      (node (ref "R55") (pin "1") (pinfunction "1_1") (pintype "passive"))
      (node (ref "SD1") (pin "9") (pinfunction "~{CARD}_9") (pintype "passive"))
    )
    (net (code "46") (name "Net-(T1A-D)") (class "Default")
      (node (ref "T1") (pin "1") (pinfunction "D_1") (pintype "passive"))
      (node (ref "T1") (pin "8") (pinfunction "D_8") (pintype "passive"))
    )
    (net (code "47") (name "Net-(T1A-G)") (class "Default")
      (node (ref "T1") (pin "4") (pinfunction "G_4") (pintype "passive"))
      (node (ref "U$7") (pin "1") (pinfunction "0D_1") (pintype "bidirectional"))
    )
    (net (code "48") (name "Net-(T1B-G)") (class "Default")
      (node (ref "T1") (pin "5") (pinfunction "G_5") (pintype "passive"))
      (node (ref "U$7") (pin "3") (pinfunction "0C_3") (pintype "bidirectional"))
    )
    (net (code "49") (name "Net-(U$1-NRST)") (class "Default")
      (node (ref "C25") (pin "2") (pinfunction "2_2") (pintype "passive"))
      (node (ref "R21") (pin "1") (pinfunction "1_1") (pintype "passive"))
      (node (ref "S2") (pin "3") (pinfunction "3_3") (pintype "passive"))
      (node (ref "S2") (pin "4") (pinfunction "4_4") (pintype "passive"))
      (node (ref "U$1") (pin "7") (pinfunction "NRST_7") (pintype "bidirectional"))
    )
    (net (code "50") (name "Net-(U$1-PA4{slash}ADC12_IN4)") (class "Default")
      (node (ref "R37") (pin "1") (pinfunction "1_1") (pintype "passive"))
      (node (ref "U$1") (pin "20") (pinfunction "PA4/ADC12_IN4_20") (pintype "bidirectional"))
    )
    (net (code "51") (name "Net-(U$1-PA5{slash}ADC12_IN5)") (class "Default")
      (node (ref "R67") (pin "1") (pinfunction "1_1") (pintype "passive"))
      (node (ref "U$1") (pin "21") (pinfunction "PA5/ADC12_IN5_21") (pintype "bidirectional"))
    )
    (net (code "52") (name "Net-(U$1-PB8{slash}TIM10_CH1{slash}TIM4_CH3(5T))") (class "Default")
      (node (ref "D1") (pin "C") (pinfunction "C_C") (pintype "passive"))
      (node (ref "U$1") (pin "61") (pinfunction "PB8/TIM10_CH1/TIM4_CH3(5T)_61") (pintype "bidirectional"))
    )
    (net (code "53") (name "Net-(U$1-PB9{slash}TIM11_CH1{slash}TIM4_CH4(5T))") (class "Default")
      (node (ref "D2") (pin "C") (pinfunction "C_C") (pintype "passive"))
      (node (ref "U$1") (pin "62") (pinfunction "PB9/TIM11_CH1/TIM4_CH4(5T)_62") (pintype "bidirectional"))
    )
    (net (code "54") (name "Net-(U$1-PC0{slash}ADC123_IN10(5T))") (class "Default")
      (node (ref "R36") (pin "2") (pinfunction "2_2") (pintype "passive"))
      (node (ref "U$1") (pin "8") (pinfunction "PC0/ADC123_IN10(5T)_8") (pintype "bidirectional"))
    )
    (net (code "55") (name "Net-(U$1-VCAP_1)") (class "Default")
      (node (ref "C23") (pin "2") (pinfunction "2_2") (pintype "passive"))
      (node (ref "U$1") (pin "31") (pinfunction "VCAP_1_31") (pintype "bidirectional"))
    )
    (net (code "56") (name "Net-(U$1-VCAP_2)") (class "Default")
      (node (ref "C24") (pin "2") (pinfunction "2_2") (pintype "passive"))
      (node (ref "U$1") (pin "47") (pinfunction "VCAP_2_47") (pintype "bidirectional"))
    )
    (net (code "57") (name "Net-(U$4-1.IN)") (class "Default")
      (node (ref "SW1") (pin "CH1A") (pinfunction "CH1A_CH1A") (pintype "bidirectional"))
      (node (ref "U$4") (pin "1") (pinfunction "1.IN_1") (pintype "bidirectional"))
    )
    (net (code "58") (name "Net-(U$5-1.IN)") (class "Default")
      (node (ref "U$5") (pin "1") (pinfunction "1.IN_1") (pintype "bidirectional"))
      (node (ref "U4") (pin "VBUS1") (pinfunction "VBUS_VBUS1") (pintype "bidirectional"))
    )
    (net (code "59") (name "Net-(U$5-2.OUT)") (class "Default")
      (node (ref "R28") (pin "2") (pinfunction "2_2") (pintype "passive"))
      (node (ref "U$5") (pin "2") (pinfunction "2.OUT_2") (pintype "bidirectional"))
    )
    (net (code "60") (name "Net-(U$6-PROG)") (class "Default")
      (node (ref "R62") (pin "2") (pinfunction "2_2") (pintype "passive"))
      (node (ref "U$6") (pin "2") (pinfunction "PROG_2") (pintype "bidirectional"))
    )
    (net (code "61") (name "Net-(U$6-~{CHRG})") (class "Default")
      (node (ref "R63") (pin "1") (pinfunction "1_1") (pintype "passive"))
      (node (ref "U$6") (pin "7") (pinfunction "~{CHRG}_7") (pintype "bidirectional"))
    )
    (net (code "62") (name "Net-(U$6-~{STDBY})") (class "Default")
      (node (ref "R64") (pin "1") (pinfunction "1_1") (pintype "passive"))
      (node (ref "U$6") (pin "6") (pinfunction "~{STDBY}_6") (pintype "bidirectional"))
    )
    (net (code "63") (name "Net-(U$7-CS)") (class "Default")
      (node (ref "R66") (pin "2") (pinfunction "2_2") (pintype "passive"))
      (node (ref "U$7") (pin "2") (pinfunction "CS_2") (pintype "bidirectional"))
    )
    (net (code "64") (name "Net-(U$7-GND)") (class "Default")
      (node (ref "BT1") (pin "-") (pinfunction "-_-") (pintype "power_in"))
      (node (ref "C1") (pin "-") (pinfunction "-_-") (pintype "passive"))
      (node (ref "C40") (pin "2") (pinfunction "2_2") (pintype "passive"))
      (node (ref "T1") (pin "2") (pinfunction "S_2") (pintype "passive"))
      (node (ref "T1") (pin "3") (pinfunction "S_3") (pintype "passive"))
      (node (ref "U$7") (pin "6") (pinfunction "GND_6") (pintype "bidirectional"))
    )
    (net (code "65") (name "Net-(U$7-VCC)") (class "Default")
      (node (ref "C40") (pin "1") (pinfunction "1_1") (pintype "passive"))
      (node (ref "R65") (pin "1") (pinfunction "1_1") (pintype "passive"))
      (node (ref "U$7") (pin "5") (pinfunction "VCC_5") (pintype "bidirectional"))
    )
    (net (code "66") (name "Net-(U$9-2-OUTL)") (class "Default")
      (node (ref "C14") (pin "-") (pinfunction "-_-") (pintype "passive"))
      (node (ref "U$9") (pin "2") (pinfunction "2-OUTL_2") (pintype "bidirectional"))
      (node (ref "U$9") (pin "5") (pinfunction "5-OUTR_5") (pintype "bidirectional"))
      (node (ref "U$9") (pin "6") (pinfunction "6-OUTL_6") (pintype "bidirectional"))
    )
    (net (code "67") (name "Net-(U$18-2.C2P)") (class "Default")
      (node (ref "C15") (pin "2") (pinfunction "2_2") (pintype "passive"))
      (node (ref "U$18") (pin "P$2") (pinfunction "2.C2P_P$2") (pintype "bidirectional"))
    )
    (net (code "68") (name "Net-(U$18-3.C2N)") (class "Default")
      (node (ref "C15") (pin "1") (pinfunction "1_1") (pintype "passive"))
      (node (ref "U$18") (pin "P$3") (pinfunction "3.C2N_P$3") (pintype "bidirectional"))
    )
    (net (code "69") (name "Net-(U$18-4.C1P)") (class "Default")
      (node (ref "C36") (pin "2") (pinfunction "2_2") (pintype "passive"))
      (node (ref "U$18") (pin "P$4") (pinfunction "4.C1P_P$4") (pintype "bidirectional"))
    )
    (net (code "70") (name "Net-(U$18-5.C1N)") (class "Default")
      (node (ref "C36") (pin "1") (pinfunction "1_1") (pintype "passive"))
      (node (ref "U$18") (pin "P$5") (pinfunction "5.C1N_P$5") (pintype "bidirectional"))
    )
    (net (code "71") (name "Net-(U$18-14.RES#)") (class "Default")
      (node (ref "C2") (pin "2") (pinfunction "2_2") (pintype "passive"))
      (node (ref "R38") (pin "2") (pinfunction "2_2") (pintype "passive"))
      (node (ref "U$18") (pin "P$14") (pinfunction "14.RES#_P$14") (pintype "bidirectional"))
    )
    (net (code "72") (name "Net-(U$18-26.IREF)") (class "Default")
      (node (ref "R39") (pin "1") (pinfunction "1_1") (pintype "passive"))
      (node (ref "U$18") (pin "P$26") (pinfunction "26.IREF_P$26") (pintype "bidirectional"))
    )
    (net (code "73") (name "Net-(U$18-27.VCOMH)") (class "Default")
      (node (ref "C22") (pin "2") (pinfunction "2_2") (pintype "passive"))
      (node (ref "U$18") (pin "P$27") (pinfunction "27.VCOMH_P$27") (pintype "bidirectional"))
    )
    (net (code "74") (name "Net-(U$18-28.VCC)") (class "Default")
      (node (ref "C37") (pin "2") (pinfunction "2_2") (pintype "passive"))
      (node (ref "U$18") (pin "P$28") (pinfunction "28.VCC_P$28") (pintype "bidirectional"))
    )
    (net (code "75") (name "Net-(U2A-+IN1)") (class "Default")
      (node (ref "R14") (pin "1") (pinfunction "1_1") (pintype "passive"))
      (node (ref "R15") (pin "2") (pinfunction "2_2") (pintype "passive"))
      (node (ref "R6") (pin "1") (pinfunction "1_1") (pintype "passive"))
      (node (ref "U2") (pin "3") (pinfunction "+IN1_3") (pintype "input"))
    )
    (net (code "76") (name "Net-(U2A--IN1)") (class "Default")
      (node (ref "R19") (pin "2") (pinfunction "2_2") (pintype "passive"))
      (node (ref "R22") (pin "1") (pinfunction "1_1") (pintype "passive"))
      (node (ref "U2") (pin "2") (pinfunction "-IN1_2") (pintype "input"))
    )
    (net (code "77") (name "Net-(U2A-OUT1)") (class "Default")
      (node (ref "R19") (pin "1") (pinfunction "1_1") (pintype "passive"))
      (node (ref "R25") (pin "2") (pinfunction "2_2") (pintype "passive"))
      (node (ref "U2") (pin "1") (pinfunction "OUT1_1") (pintype "output"))
    )
    (net (code "78") (name "Net-(U2B-+IN2)") (class "Default")
      (node (ref "C42") (pin "1") (pinfunction "1_1") (pintype "passive"))
      (node (ref "R24") (pin "1") (pinfunction "1_1") (pintype "passive"))
      (node (ref "U2") (pin "5") (pinfunction "+IN2_5") (pintype "input"))
    )
    (net (code "79") (name "Net-(U2C-+IN2)") (class "Default")
      (node (ref "R16") (pin "1") (pinfunction "1_1") (pintype "passive"))
      (node (ref "R17") (pin "2") (pinfunction "2_2") (pintype "passive"))
      (node (ref "R18") (pin "1") (pinfunction "1_1") (pintype "passive"))
      (node (ref "U2") (pin "10") (pinfunction "+IN2_10") (pintype "input"))
    )
    (net (code "80") (name "Net-(U2C--IN2)") (class "Default")
      (node (ref "R20") (pin "2") (pinfunction "2_2") (pintype "passive"))
      (node (ref "R23") (pin "1") (pinfunction "1_1") (pintype "passive"))
      (node (ref "U2") (pin "9") (pinfunction "-IN2_9") (pintype "input"))
    )
    (net (code "81") (name "Net-(U2C-OUT2)") (class "Default")
      (node (ref "R20") (pin "1") (pinfunction "1_1") (pintype "passive"))
      (node (ref "R30") (pin "2") (pinfunction "2_2") (pintype "passive"))
      (node (ref "U2") (pin "8") (pinfunction "OUT2_8") (pintype "output"))
    )
    (net (code "82") (name "Net-(U2D-+IN2)") (class "Default")
      (node (ref "C32") (pin "1") (pinfunction "1_1") (pintype "passive"))
      (node (ref "R31") (pin "1") (pinfunction "1_1") (pintype "passive"))
      (node (ref "U2") (pin "12") (pinfunction "+IN2_12") (pintype "input"))
    )
    (net (code "83") (name "Net-(U4-D+)") (class "Default")
      (node (ref "R27") (pin "2") (pinfunction "2_2") (pintype "passive"))
      (node (ref "U4") (pin "D+1") (pinfunction "D+_D+1") (pintype "bidirectional"))
    )
    (net (code "84") (name "Net-(U4-D-)") (class "Default")
      (node (ref "R26") (pin "2") (pinfunction "2_2") (pintype "passive"))
      (node (ref "U4") (pin "D-1") (pinfunction "D-_D-1") (pintype "bidirectional"))
    )
    (net (code "85") (name "Net-(U4-USBID)") (class "Default")
      (node (ref "R29") (pin "2") (pinfunction "2_2") (pintype "passive"))
      (node (ref "U4") (pin "ID1") (pinfunction "USBID_ID1") (pintype "bidirectional"))
    )
    (net (code "86") (name "OSC32_IN") (class "Default")
      (node (ref "C3") (pin "2") (pinfunction "2_2") (pintype "passive"))
      (node (ref "U$1") (pin "3") (pinfunction "PC14/OSC32_IN(5T)_3") (pintype "bidirectional"))
      (node (ref "U$2") (pin "1") (pinfunction "1.XIN_1") (pintype "bidirectional"))
    )
    (net (code "87") (name "OSC32_OUT") (class "Default")
      (node (ref "C18") (pin "2") (pinfunction "2_2") (pintype "passive"))
      (node (ref "U$1") (pin "4") (pinfunction "PC15/OSC32_OUT(5T)_4") (pintype "bidirectional"))
      (node (ref "U$2") (pin "2") (pinfunction "2.XIN_2") (pintype "bidirectional"))
    )
    (net (code "88") (name "OSC_IN") (class "Default")
      (node (ref "C17") (pin "2") (pinfunction "2_2") (pintype "passive"))
      (node (ref "U$1") (pin "5") (pinfunction "PH0/OSC_IN(5T)_5") (pintype "bidirectional"))
      (node (ref "U$8") (pin "1") (pinfunction "1.XIN_1") (pintype "bidirectional"))
    )
    (net (code "89") (name "OSC_OUT") (class "Default")
      (node (ref "C16") (pin "2") (pinfunction "2_2") (pintype "passive"))
      (node (ref "U$1") (pin "6") (pinfunction "PH1/OSC_OUT(5T)_6") (pintype "bidirectional"))
      (node (ref "U$8") (pin "2") (pinfunction "2.XOUT_2") (pintype "bidirectional"))
    )
    (net (code "90") (name "OTG_FS_DM") (class "Default")
      (node (ref "R26") (pin "1") (pinfunction "1_1") (pintype "passive"))
      (node (ref "U$1") (pin "44") (pinfunction "PA11/TIM1_CH4/CANRX/USBDM(5T)_44") (pintype "bidirectional"))
    )
    (net (code "91") (name "OTG_FS_DP") (class "Default")
      (node (ref "R27") (pin "1") (pinfunction "1_1") (pintype "passive"))
      (node (ref "U$1") (pin "45") (pinfunction "PA12/CANTX/USBDP(5T)_45") (pintype "bidirectional"))
    )
    (net (code "92") (name "OTG_FS_ID") (class "Default")
      (node (ref "R29") (pin "1") (pinfunction "1_1") (pintype "passive"))
      (node (ref "U$1") (pin "43") (pinfunction "PA10/TIM1_CH3/USART1_RX(5T)_43") (pintype "bidirectional"))
    )
    (net (code "93") (name "SD_CD") (class "Default")
      (node (ref "R55") (pin "2") (pinfunction "2_2") (pintype "passive"))
      (node (ref "R61") (pin "1") (pinfunction "1_1") (pintype "passive"))
      (node (ref "U$1") (pin "36") (pinfunction "PB15/SPI2_MOSI(5T)_36") (pintype "bidirectional"))
    )
    (net (code "94") (name "SD_CLK") (class "Default")
      (node (ref "R52") (pin "1") (pinfunction "1_1") (pintype "passive"))
      (node (ref "U$1") (pin "53") (pinfunction "PC12(5T)_53") (pintype "bidirectional"))
    )
    (net (code "95") (name "SD_CMD") (class "Default")
      (node (ref "R51") (pin "1") (pinfunction "1_1") (pintype "passive"))
      (node (ref "R58") (pin "1") (pinfunction "1_1") (pintype "passive"))
      (node (ref "U$1") (pin "54") (pinfunction "PD2/TIM3_ETR(5T)_54") (pintype "bidirectional"))
    )
    (net (code "96") (name "SD_DAT0") (class "Default")
      (node (ref "R53") (pin "2") (pinfunction "2_2") (pintype "passive"))
      (node (ref "R57") (pin "1") (pinfunction "1_1") (pintype "passive"))
      (node (ref "U$1") (pin "39") (pinfunction "PC8/TIM3_CH3/TIM8_CH3(5T)_39") (pintype "bidirectional"))
    )
    (net (code "97") (name "SD_DAT1") (class "Default")
      (node (ref "R54") (pin "1") (pinfunction "1_1") (pintype "passive"))
      (node (ref "R56") (pin "1") (pinfunction "1_1") (pintype "passive"))
      (node (ref "U$1") (pin "40") (pinfunction "PC9/TIM3_CH4/TIM8_CH4(5T)_40") (pintype "bidirectional"))
    )
    (net (code "98") (name "SD_DAT2") (class "Default")
      (node (ref "R49") (pin "1") (pinfunction "1_1") (pintype "passive"))
      (node (ref "R60") (pin "1") (pinfunction "1_1") (pintype "passive"))
      (node (ref "U$1") (pin "51") (pinfunction "PC10(5T)_51") (pintype "bidirectional"))
    )
    (net (code "99") (name "SD_DAT3") (class "Default")
      (node (ref "R50") (pin "1") (pinfunction "1_1") (pintype "passive"))
      (node (ref "R59") (pin "1") (pinfunction "1_1") (pintype "passive"))
      (node (ref "U$1") (pin "52") (pinfunction "PC11(5T)_52") (pintype "bidirectional"))
    )
    (net (code "100") (name "SIGNAL") (class "Default")
      (node (ref "ASW") (pin "7") (pinfunction "1D_7") (pintype "bidirectional"))
      (node (ref "C44") (pin "2") (pinfunction "2_2") (pintype "passive"))
      (node (ref "R36") (pin "1") (pinfunction "1_1") (pintype "passive"))
    )
    (net (code "101") (name "SWTCK") (class "Default")
      (node (ref "JP1") (pin "3") (pinfunction "3_3") (pintype "passive"))
      (node (ref "U$1") (pin "49") (pinfunction "PA14/JTCK-SWCLK(5T)_49") (pintype "bidirectional"))
    )
    (net (code "102") (name "SWTDIO") (class "Default")
      (node (ref "JP1") (pin "2") (pinfunction "2_2") (pintype "passive"))
      (node (ref "U$1") (pin "46") (pinfunction "PA13/JTMS-SWDAT(5T)_46") (pintype "bidirectional"))
    )
    (net (code "103") (name "VBUS") (class "Default")
      (node (ref "C38") (pin "A") (pinfunction "+_A") (pintype "passive"))
      (node (ref "D5") (pin "A") (pinfunction "A_A") (pintype "passive"))
      (node (ref "D6") (pin "A") (pinfunction "A_A") (pintype "passive"))
      (node (ref "R28") (pin "1") (pinfunction "1_1") (pintype "passive"))
      (node (ref "U$1") (pin "42") (pinfunction "PA9/TIM1_CH2/USART1_TX(5T)_42") (pintype "bidirectional"))
      (node (ref "U$6") (pin "4") (pinfunction "VCC_4") (pintype "bidirectional"))
      (node (ref "U$6") (pin "8") (pinfunction "CE_8") (pintype "bidirectional"))
    )
    (net (code "104") (name "VCC") (class "Default")
      (node (ref "C21") (pin "2") (pinfunction "2_2") (pintype "passive"))
      (node (ref "IC1") (pin "1") (pinfunction "VIN_1") (pintype "input"))
      (node (ref "IC1") (pin "3") (pinfunction "VINH_3") (pintype "input"))
      (node (ref "R34") (pin "2") (pinfunction "2_2") (pintype "passive"))
      (node (ref "R38") (pin "1") (pinfunction "1_1") (pintype "passive"))
      (node (ref "U$18") (pin "P$11") (pinfunction "11.BS1_P$11") (pintype "bidirectional"))
      (node (ref "U$18") (pin "P$6") (pinfunction "6.VBAT_P$6") (pintype "bidirectional"))
      (node (ref "U$18") (pin "P$9") (pinfunction "9.VDD_P$9") (pintype "bidirectional"))
      (node (ref "U$4") (pin "2") (pinfunction "2.OUT_2") (pintype "bidirectional"))
    )
    (net (code "105") (name "VDDA") (class "Default")
      (node (ref "C10") (pin "2") (pinfunction "2_2") (pintype "passive"))
      (node (ref "C11") (pin "2") (pinfunction "2_2") (pintype "passive"))
      (node (ref "C12") (pin "2") (pinfunction "2_2") (pintype "passive"))
      (node (ref "C13") (pin "2") (pinfunction "2_2") (pintype "passive"))
      (node (ref "U$1") (pin "13") (pinfunction "VDDA_13") (pintype "bidirectional"))
      (node (ref "U$3") (pin "2") (pinfunction "2.OUT_2") (pintype "bidirectional"))
    )
    (net (code "106") (name "unconnected-(ASW-2D-Pad9)") (class "Default")
      (node (ref "ASW") (pin "9") (pinfunction "2D_9") (pintype "bidirectional"))
    )
    (net (code "107") (name "unconnected-(ASW-2S1-Pad10)") (class "Default")
      (node (ref "ASW") (pin "10") (pinfunction "2S1_10") (pintype "bidirectional"))
    )
    (net (code "108") (name "unconnected-(ASW-2S2-Pad11)") (class "Default")
      (node (ref "ASW") (pin "11") (pinfunction "2S2_11") (pintype "bidirectional"))
    )
    (net (code "109") (name "unconnected-(ASW-2S3-Pad12)") (class "Default")
      (node (ref "ASW") (pin "12") (pinfunction "2S3_12") (pintype "bidirectional"))
    )
    (net (code "110") (name "unconnected-(ASW-2S4-Pad13)") (class "Default")
      (node (ref "ASW") (pin "13") (pinfunction "2S4_13") (pintype "bidirectional"))
    )
    (net (code "111") (name "unconnected-(R8-CW-Pad3)") (class "Default")
      (node (ref "R8") (pin "3") (pinfunction "CW_3") (pintype "passive"))
    )
    (net (code "112") (name "unconnected-(R11-CW-Pad3)") (class "Default")
      (node (ref "R11") (pin "3") (pinfunction "CW_3") (pintype "passive"))
    )
    (net (code "113") (name "unconnected-(SW1-PadCH1B)") (class "Default")
      (node (ref "SW1") (pin "CH1B") (pinfunction "CH1B_CH1B") (pintype "bidirectional"))
    )
    (net (code "114") (name "unconnected-(SW1-PadCH2A)") (class "Default")
      (node (ref "SW1") (pin "CH2A") (pinfunction "CH2A_CH2A") (pintype "bidirectional"))
    )
    (net (code "115") (name "unconnected-(SW1-PadCH2B)") (class "Default")
      (node (ref "SW1") (pin "CH2B") (pinfunction "CH2B_CH2B") (pintype "bidirectional"))
    )
    (net (code "116") (name "unconnected-(SW1-PadCOM2)") (class "Default")
      (node (ref "SW1") (pin "COM2") (pinfunction "COM2_COM2") (pintype "bidirectional"))
    )
    (net (code "117") (name "unconnected-(U$1-PA0{slash}ADC123_IN0(5T)-Pad14)") (class "Default")
      (node (ref "U$1") (pin "14") (pinfunction "PA0/ADC123_IN0(5T)_14") (pintype "bidirectional"))
    )
    (net (code "118") (name "unconnected-(U$1-PA1{slash}ADC123_IN1(5T)-Pad15)") (class "Default")
      (node (ref "U$1") (pin "15") (pinfunction "PA1/ADC123_IN1(5T)_15") (pintype "bidirectional"))
    )
    (net (code "119") (name "unconnected-(U$1-PA2{slash}ADC123_IN2(5T)-Pad16)") (class "Default")
      (node (ref "U$1") (pin "16") (pinfunction "PA2/ADC123_IN2(5T)_16") (pintype "bidirectional"))
    )
    (net (code "120") (name "unconnected-(U$1-PA3{slash}ADC123_IN3(5T)-Pad17)") (class "Default")
      (node (ref "U$1") (pin "17") (pinfunction "PA3/ADC123_IN3(5T)_17") (pintype "bidirectional"))
    )
    (net (code "121") (name "unconnected-(U$1-PA6{slash}ADC12_IN6(5T)-Pad22)") (class "Default")
      (node (ref "U$1") (pin "22") (pinfunction "PA6/ADC12_IN6(5T)_22") (pintype "bidirectional"))
    )
    (net (code "122") (name "unconnected-(U$1-PA7{slash}TIM1_CH1N{slash}ADC12_IN7(FT)-Pad23)") (class "Default")
      (node (ref "U$1") (pin "23") (pinfunction "PA7/TIM1_CH1N/ADC12_IN7(FT)_23") (pintype "bidirectional"))
    )
    (net (code "123") (name "unconnected-(U$1-PA8{slash}TIM1_CH1(5T)-Pad41)") (class "Default")
      (node (ref "U$1") (pin "41") (pinfunction "PA8/TIM1_CH1(5T)_41") (pintype "bidirectional"))
    )
    (net (code "124") (name "unconnected-(U$1-PA15{slash}JTDI(5T)-Pad50)") (class "Default")
      (node (ref "U$1") (pin "50") (pinfunction "PA15/JTDI(5T)_50") (pintype "bidirectional"))
    )
    (net (code "125") (name "unconnected-(U$1-PB0{slash}TIM1_CH2N{slash}ADC12_IN8(5T)-Pad26)") (class "Default")
      (node (ref "U$1") (pin "26") (pinfunction "PB0/TIM1_CH2N/ADC12_IN8(5T)_26") (pintype "bidirectional"))
    )
    (net (code "126") (name "unconnected-(U$1-PB1{slash}TIM1_CH3N{slash}ADC12_IN9(5T)-Pad27)") (class "Default")
      (node (ref "U$1") (pin "27") (pinfunction "PB1/TIM1_CH3N/ADC12_IN9(5T)_27") (pintype "bidirectional"))
    )
    (net (code "127") (name "unconnected-(U$1-PB3{slash}JTDO(5T)-Pad55)") (class "Default")
      (node (ref "U$1") (pin "55") (pinfunction "PB3/JTDO(5T)_55") (pintype "bidirectional"))
    )
    (net (code "128") (name "unconnected-(U$1-PB4{slash}JNTRST(5T)-Pad56)") (class "Default")
      (node (ref "U$1") (pin "56") (pinfunction "PB4/JNTRST(5T)_56") (pintype "bidirectional"))
    )
    (net (code "129") (name "unconnected-(U$1-PB10{slash}I2C2_SCL(5T)-Pad29)") (class "Default")
      (node (ref "U$1") (pin "29") (pinfunction "PB10/I2C2_SCL(5T)_29") (pintype "bidirectional"))
    )
    (net (code "130") (name "unconnected-(U$1-PB11{slash}I2C2_SDA(5T)-Pad30)") (class "Default")
      (node (ref "U$1") (pin "30") (pinfunction "PB11/I2C2_SDA(5T)_30") (pintype "bidirectional"))
    )
    (net (code "131") (name "unconnected-(U$1-PB12(5T)-Pad33)") (class "Default")
      (node (ref "U$1") (pin "33") (pinfunction "PB12(5T)_33") (pintype "bidirectional"))
    )
    (net (code "132") (name "unconnected-(U$1-PB13{slash}SPI2_SCK(5T)-Pad34)") (class "Default")
      (node (ref "U$1") (pin "34") (pinfunction "PB13/SPI2_SCK(5T)_34") (pintype "bidirectional"))
    )
    (net (code "133") (name "unconnected-(U$1-PB14{slash}SPI2_MISO(5T)-Pad35)") (class "Default")
      (node (ref "U$1") (pin "35") (pinfunction "PB14/SPI2_MISO(5T)_35") (pintype "bidirectional"))
    )
    (net (code "134") (name "unconnected-(U$1-PC1{slash}ADC123_IN11(5T)-Pad9)") (class "Default")
      (node (ref "U$1") (pin "9") (pinfunction "PC1/ADC123_IN11(5T)_9") (pintype "bidirectional"))
    )
    (net (code "135") (name "unconnected-(U$1-PC2{slash}ADC123_IN12(5T)-Pad10)") (class "Default")
      (node (ref "U$1") (pin "10") (pinfunction "PC2/ADC123_IN12(5T)_10") (pintype "bidirectional"))
    )
    (net (code "136") (name "unconnected-(U$1-PC3{slash}ADC123_IN13(5T)-Pad11)") (class "Default")
      (node (ref "U$1") (pin "11") (pinfunction "PC3/ADC123_IN13(5T)_11") (pintype "bidirectional"))
    )
    (net (code "137") (name "unconnected-(U$1-PC4{slash}ADC12_IN14-Pad24)") (class "Default")
      (node (ref "U$1") (pin "24") (pinfunction "PC4/ADC12_IN14_24") (pintype "bidirectional"))
    )
    (net (code "138") (name "unconnected-(U$1-PC5{slash}ADC12_IN15-Pad25)") (class "Default")
      (node (ref "U$1") (pin "25") (pinfunction "PC5/ADC12_IN15_25") (pintype "bidirectional"))
    )
    (net (code "139") (name "unconnected-(U$7-TD-Pad4)") (class "Default")
      (node (ref "U$7") (pin "4") (pinfunction "TD_4") (pintype "bidirectional"))
    )
    (net (code "140") (name "unconnected-(U$18-1.NC(GND)-PadP$1)") (class "Default")
      (node (ref "U$18") (pin "P$1") (pinfunction "1.NC(GND)_P$1") (pintype "bidirectional"))
    )
    (net (code "141") (name "unconnected-(U$18-7.NC-PadP$7)") (class "Default")
      (node (ref "U$18") (pin "P$7") (pinfunction "7.NC_P$7") (pintype "bidirectional"))
    )
    (net (code "142") (name "unconnected-(U$18-30.NC(GND)-PadP$30)") (class "Default")
      (node (ref "U$18") (pin "P$30") (pinfunction "30.NC(GND)_P$30") (pintype "bidirectional"))
    )
  )
)
